# DAC.net
KiCad netlist of a schematic drawn in Altium Designer
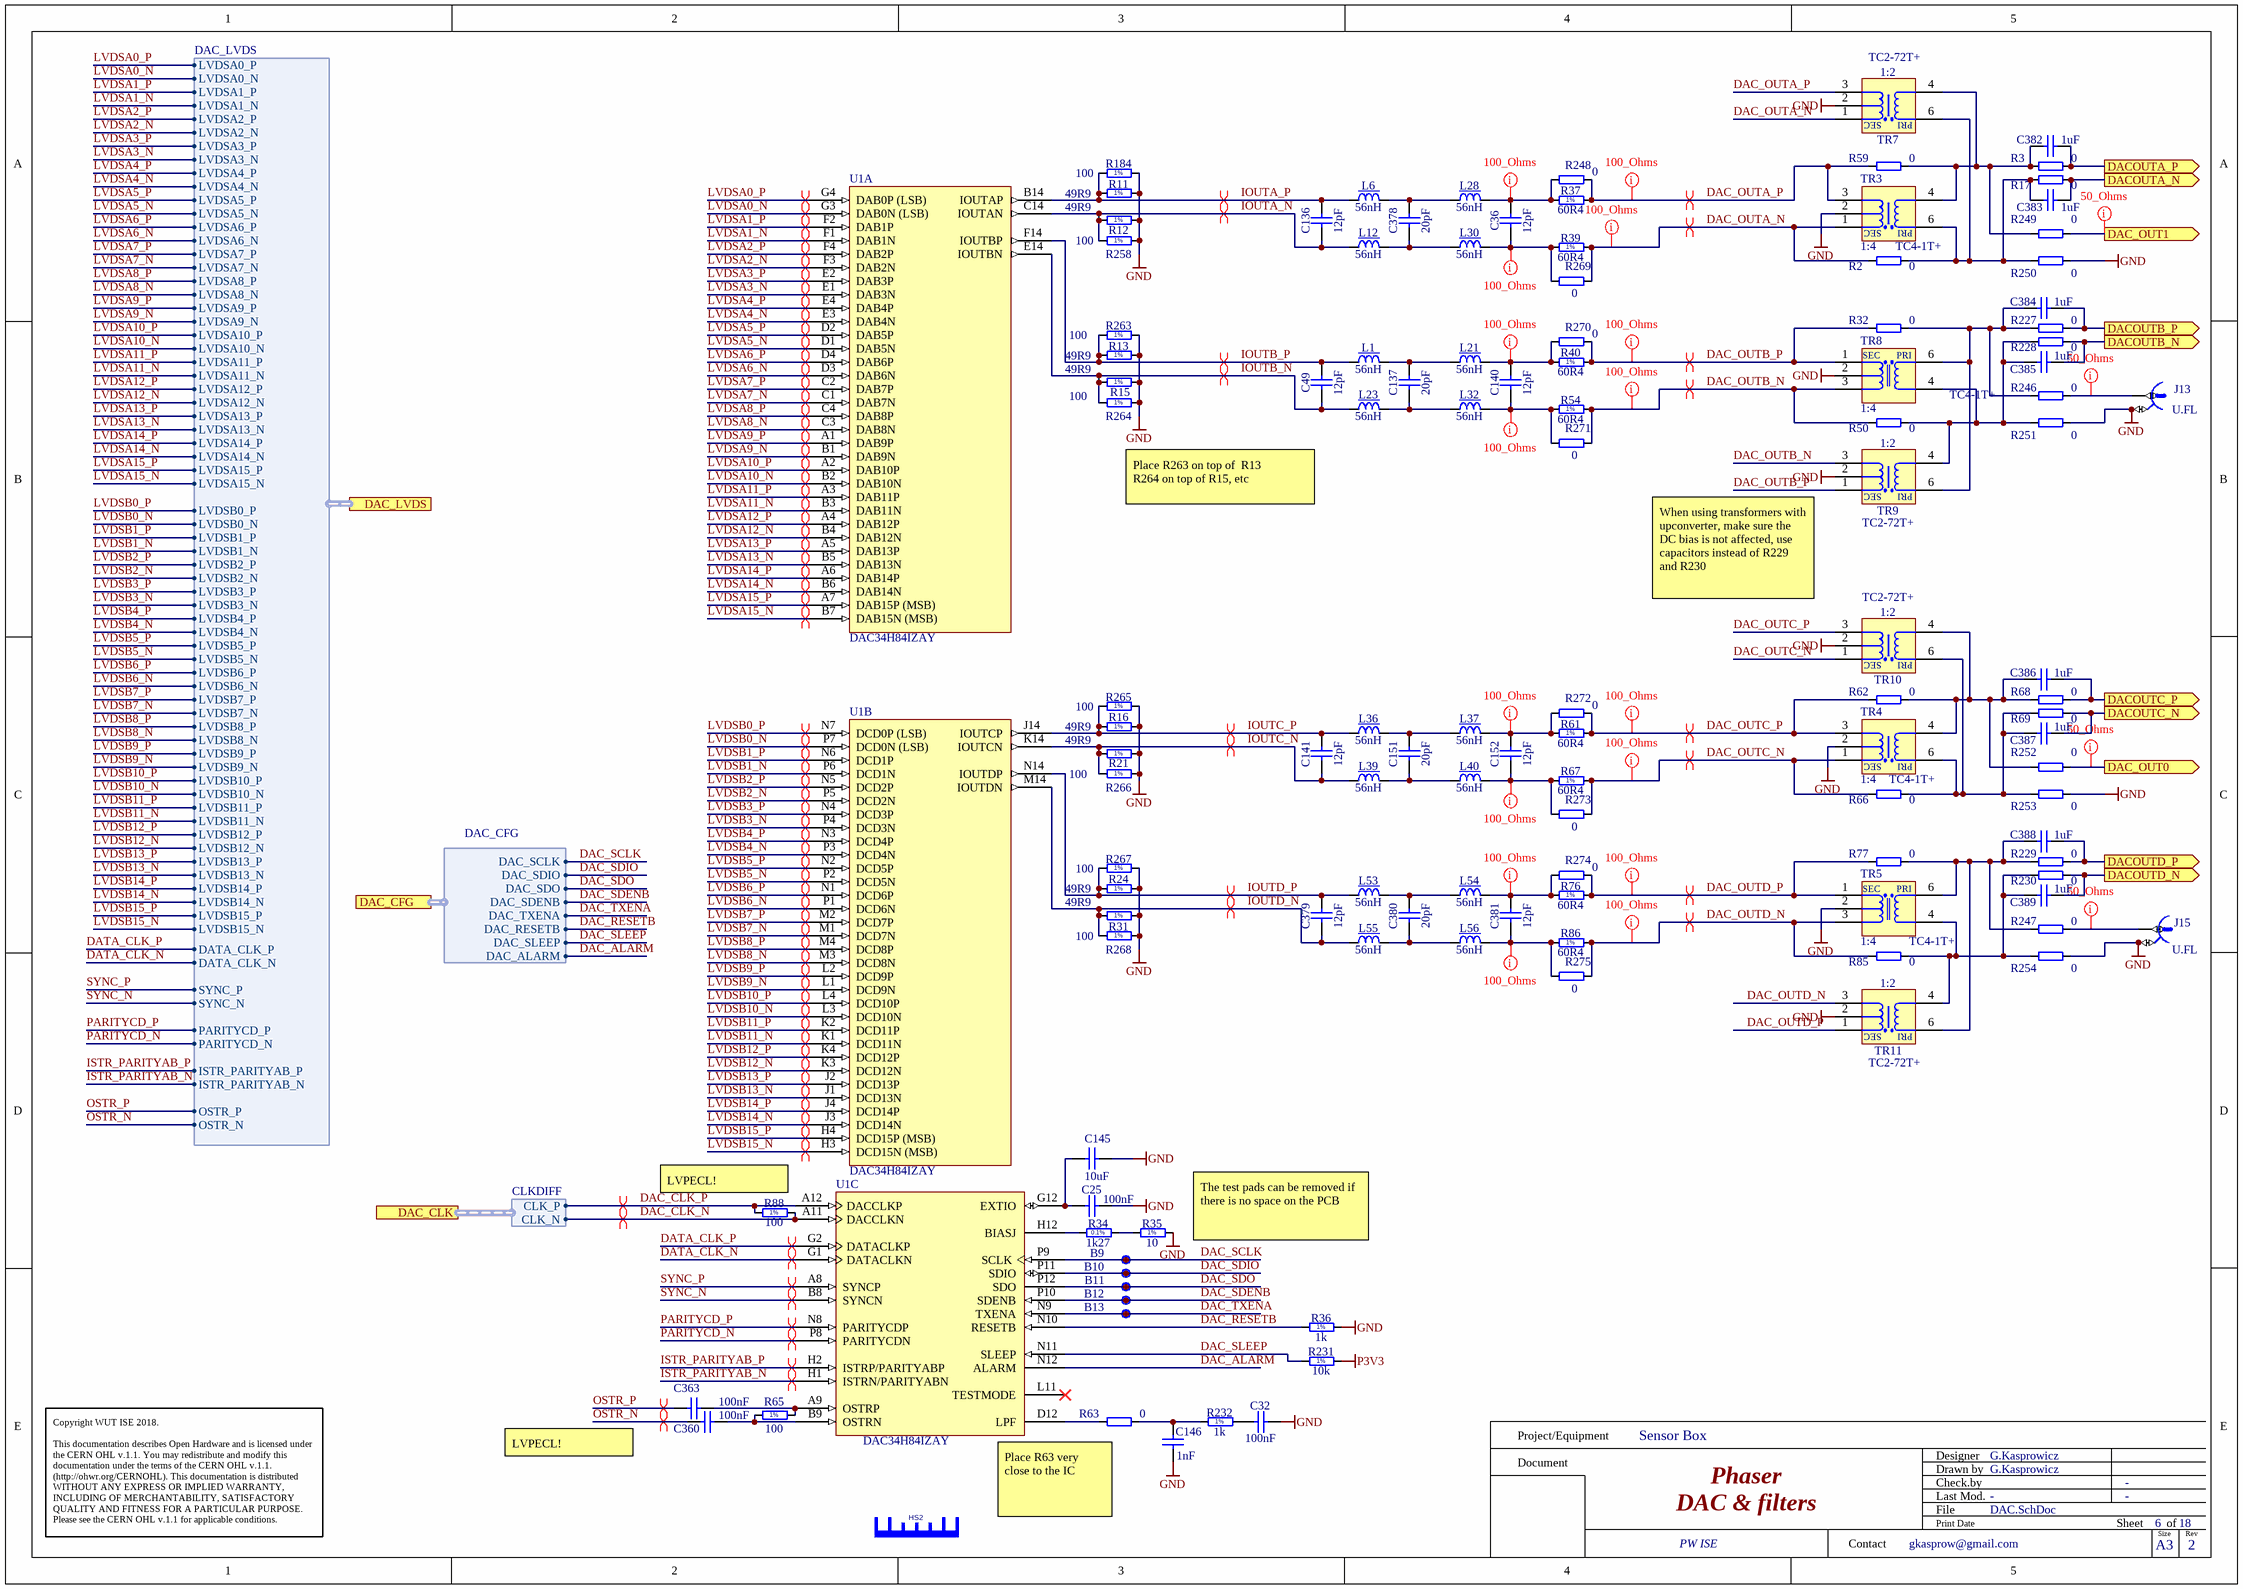
[diagram p0: DAC.SchDoc]

(export (version "E")
  (design (tool "Eeschema 10.0.6"))
  (components
    (comp (ref "B9")
      (value "SMD Pad")
      (footprint "C100")
      (description "Through Hole Pad")
      (fields (field (name "PART NUMBER") "SMD_PAD_D1MM") (field (name "AUTHOR") "CERN DEM JLC"))
      (libsource (lib "Eletro-mechanical") (part "Single SMD Pad (Round)"))
    )
    (comp (ref "B10")
      (value "SMD Pad")
      (footprint "C100")
      (description "Through Hole Pad")
      (fields (field (name "PART NUMBER") "SMD_PAD_D1MM") (field (name "AUTHOR") "CERN DEM JLC"))
      (libsource (lib "Eletro-mechanical") (part "Single SMD Pad (Round)"))
    )
    (comp (ref "B11")
      (value "SMD Pad")
      (footprint "C100")
      (description "Through Hole Pad")
      (fields (field (name "PART NUMBER") "SMD_PAD_D1MM") (field (name "AUTHOR") "CERN DEM JLC"))
      (libsource (lib "Eletro-mechanical") (part "Single SMD Pad (Round)"))
    )
    (comp (ref "B12")
      (value "SMD Pad")
      (footprint "C100")
      (description "Through Hole Pad")
      (fields (field (name "PART NUMBER") "SMD_PAD_D1MM") (field (name "AUTHOR") "CERN DEM JLC"))
      (libsource (lib "Eletro-mechanical") (part "Single SMD Pad (Round)"))
    )
    (comp (ref "B13")
      (value "SMD Pad")
      (footprint "C100")
      (description "Through Hole Pad")
      (fields (field (name "PART NUMBER") "SMD_PAD_D1MM") (field (name "AUTHOR") "CERN DEM JLC"))
      (libsource (lib "Eletro-mechanical") (part "Single SMD Pad (Round)"))
    )
    (comp (ref "C25")
      (value "100nF")
      (footprint "CAPC1005X55N")
      (description "Non-polarised capacitor")
      (fields
        (field (name "PART NUMBER") "CC0402_100NF_16V_10%_X5R")
        (field (name "VOLTAGE") "16V")
        (field (name "AUTHOR") "CERN DEM JLC")
      )
      (libsource (lib "Capacitors") (part "Capacitor - non polarized"))
    )
    (comp (ref "C32")
      (value "100nF")
      (footprint "CAPC1608X90N")
      (description "Non-polarised capacitor")
      (fields
        (field (name "PART NUMBER") "CC0603_100NF_100V_10%_X7R")
        (field (name "VOLTAGE") "100V")
        (field (name "AUTHOR") "CERN DEM JLC")
      )
      (libsource (lib "Capacitors") (part "Capacitor - non polarized"))
    )
    (comp (ref "C36")
      (value "12pF")
      (footprint "CAPC1608X87N")
      (description "Non-polarised capacitor")
      (fields
        (field (name "PART NUMBER") "CC0603_12PF_50V_1%_NP0")
        (field (name "VOLTAGE") "50V")
        (field (name "AUTHOR") "GK")
      )
      (libsource (lib "Passives_RC") (part "CC0603_12PF_50V_1%_NP0"))
    )
    (comp (ref "C49")
      (value "12pF")
      (footprint "CAPC1608X87N")
      (description "Non-polarised capacitor")
      (fields
        (field (name "PART NUMBER") "CC0603_12PF_50V_1%_NP0")
        (field (name "VOLTAGE") "50V")
        (field (name "AUTHOR") "GK")
      )
      (libsource (lib "Passives_RC") (part "CC0603_12PF_50V_1%_NP0"))
    )
    (comp (ref "C136")
      (value "12pF")
      (footprint "CAPC1608X87N")
      (description "Non-polarised capacitor")
      (fields
        (field (name "PART NUMBER") "CC0603_12PF_50V_1%_NP0")
        (field (name "VOLTAGE") "50V")
        (field (name "AUTHOR") "GK")
      )
      (libsource (lib "Passives_RC") (part "CC0603_12PF_50V_1%_NP0"))
    )
    (comp (ref "C137")
      (value "20pF")
      (footprint "CAPC1608X87N")
      (description "Non-polarised capacitor")
      (fields
        (field (name "PART NUMBER") "CC0603_20PF_50V_1%_NP0")
        (field (name "VOLTAGE") "50V")
        (field (name "AUTHOR") "GK")
      )
      (libsource (lib "Passives_RC") (part "CC0603_20PF_50V_1%_NP0"))
    )
    (comp (ref "C140")
      (value "12pF")
      (footprint "CAPC1608X87N")
      (description "Non-polarised capacitor")
      (fields
        (field (name "PART NUMBER") "CC0603_12PF_50V_1%_NP0")
        (field (name "VOLTAGE") "50V")
        (field (name "AUTHOR") "GK")
      )
      (libsource (lib "Passives_RC") (part "CC0603_12PF_50V_1%_NP0"))
    )
    (comp (ref "C141")
      (value "12pF")
      (footprint "CAPC1608X87N")
      (description "Non-polarised capacitor")
      (fields
        (field (name "PART NUMBER") "CC0603_12PF_50V_1%_NP0")
        (field (name "VOLTAGE") "50V")
        (field (name "AUTHOR") "GK")
      )
      (libsource (lib "Passives_RC") (part "CC0603_12PF_50V_1%_NP0"))
    )
    (comp (ref "C145")
      (value "10uF")
      (footprint "CAPC2012X95N")
      (description "Non-polarised capacitor")
      (fields
        (field (name "PART NUMBER") "CC0805_10UF_25V_10%_X5R")
        (field (name "VOLTAGE") "25V")
        (field (name "AUTHOR") "CERN DEM JLC")
      )
      (libsource (lib "Capacitors") (part "Capacitor - non polarized"))
    )
    (comp (ref "C146")
      (value "1nF")
      (footprint "CAPC1608X90N")
      (description "Non-polarised capacitor")
      (fields
        (field (name "PART NUMBER") "CC0603_1NF_50V_1%_NP0")
        (field (name "VOLTAGE") "50V")
        (field (name "AUTHOR") "CERN DEM JLC")
      )
      (libsource (lib "Capacitors") (part "Capacitor - non polarized"))
    )
    (comp (ref "C151")
      (value "20pF")
      (footprint "CAPC1608X87N")
      (description "Non-polarised capacitor")
      (fields
        (field (name "PART NUMBER") "CC0603_20PF_50V_1%_NP0")
        (field (name "VOLTAGE") "50V")
        (field (name "AUTHOR") "GK")
      )
      (libsource (lib "Passives_RC") (part "CC0603_20PF_50V_1%_NP0"))
    )
    (comp (ref "C152")
      (value "12pF")
      (footprint "CAPC1608X87N")
      (description "Non-polarised capacitor")
      (fields
        (field (name "PART NUMBER") "CC0603_12PF_50V_1%_NP0")
        (field (name "VOLTAGE") "50V")
        (field (name "AUTHOR") "GK")
      )
      (libsource (lib "Passives_RC") (part "CC0603_12PF_50V_1%_NP0"))
    )
    (comp (ref "C360")
      (value "100nF")
      (footprint "CAPC1005X55N")
      (description "Non-polarised capacitor")
      (fields
        (field (name "PART NUMBER") "CC0402_100NF_16V_10%_X5R")
        (field (name "VOLTAGE") "16V")
        (field (name "AUTHOR") "CERN DEM JLC")
      )
      (libsource (lib "Capacitors") (part "Capacitor - non polarized"))
    )
    (comp (ref "C363")
      (value "100nF")
      (footprint "CAPC1005X55N")
      (description "Non-polarised capacitor")
      (fields
        (field (name "PART NUMBER") "CC0402_100NF_16V_10%_X5R")
        (field (name "VOLTAGE") "16V")
        (field (name "AUTHOR") "CERN DEM JLC")
      )
      (libsource (lib "Capacitors") (part "Capacitor - non polarized"))
    )
    (comp (ref "C378")
      (value "20pF")
      (footprint "CAPC1608X87N")
      (description "Non-polarised capacitor")
      (fields
        (field (name "PART NUMBER") "CC0603_20PF_50V_1%_NP0")
        (field (name "VOLTAGE") "50V")
        (field (name "AUTHOR") "GK")
      )
      (libsource (lib "Passives_RC") (part "CC0603_20PF_50V_1%_NP0"))
    )
    (comp (ref "C379")
      (value "12pF")
      (footprint "CAPC1608X87N")
      (description "Non-polarised capacitor")
      (fields
        (field (name "PART NUMBER") "CC0603_12PF_50V_1%_NP0")
        (field (name "VOLTAGE") "50V")
        (field (name "AUTHOR") "GK")
      )
      (libsource (lib "Passives_RC") (part "CC0603_12PF_50V_1%_NP0"))
    )
    (comp (ref "C380")
      (value "20pF")
      (footprint "CAPC1608X87N")
      (description "Non-polarised capacitor")
      (fields
        (field (name "PART NUMBER") "CC0603_20PF_50V_1%_NP0")
        (field (name "VOLTAGE") "50V")
        (field (name "AUTHOR") "GK")
      )
      (libsource (lib "Passives_RC") (part "CC0603_20PF_50V_1%_NP0"))
    )
    (comp (ref "C381")
      (value "12pF")
      (footprint "CAPC1608X87N")
      (description "Non-polarised capacitor")
      (fields
        (field (name "PART NUMBER") "CC0603_12PF_50V_1%_NP0")
        (field (name "VOLTAGE") "50V")
        (field (name "AUTHOR") "GK")
      )
      (libsource (lib "Passives_RC") (part "CC0603_12PF_50V_1%_NP0"))
    )
    (comp (ref "C382")
      (value "1uF")
      (footprint "CAPC1005X55N")
      (description "Non-polarised capacitor")
      (fields
        (field (name "PART NUMBER") "CC0402_1UF_16V_10%_X5R")
        (field (name "VOLTAGE") "16V")
        (field (name "AUTHOR") "CERN DEM JLC")
      )
      (libsource (lib "Capacitors") (part "Capacitor - non polarized"))
    )
    (comp (ref "C383")
      (value "1uF")
      (footprint "CAPC1005X55N")
      (description "Non-polarised capacitor")
      (fields
        (field (name "PART NUMBER") "CC0402_1UF_16V_10%_X5R")
        (field (name "VOLTAGE") "16V")
        (field (name "AUTHOR") "CERN DEM JLC")
      )
      (libsource (lib "Capacitors") (part "Capacitor - non polarized"))
    )
    (comp (ref "C384")
      (value "1uF")
      (footprint "CAPC1005X55N")
      (description "Non-polarised capacitor")
      (fields
        (field (name "PART NUMBER") "CC0402_1UF_16V_10%_X5R")
        (field (name "VOLTAGE") "16V")
        (field (name "AUTHOR") "CERN DEM JLC")
      )
      (libsource (lib "Capacitors") (part "Capacitor - non polarized"))
    )
    (comp (ref "C385")
      (value "1uF")
      (footprint "CAPC1005X55N")
      (description "Non-polarised capacitor")
      (fields
        (field (name "PART NUMBER") "CC0402_1UF_16V_10%_X5R")
        (field (name "VOLTAGE") "16V")
        (field (name "AUTHOR") "CERN DEM JLC")
      )
      (libsource (lib "Capacitors") (part "Capacitor - non polarized"))
    )
    (comp (ref "C386")
      (value "1uF")
      (footprint "CAPC1005X55N")
      (description "Non-polarised capacitor")
      (fields
        (field (name "PART NUMBER") "CC0402_1UF_16V_10%_X5R")
        (field (name "VOLTAGE") "16V")
        (field (name "AUTHOR") "CERN DEM JLC")
      )
      (libsource (lib "Capacitors") (part "Capacitor - non polarized"))
    )
    (comp (ref "C387")
      (value "1uF")
      (footprint "CAPC1005X55N")
      (description "Non-polarised capacitor")
      (fields
        (field (name "PART NUMBER") "CC0402_1UF_16V_10%_X5R")
        (field (name "VOLTAGE") "16V")
        (field (name "AUTHOR") "CERN DEM JLC")
      )
      (libsource (lib "Capacitors") (part "Capacitor - non polarized"))
    )
    (comp (ref "C388")
      (value "1uF")
      (footprint "CAPC1005X55N")
      (description "Non-polarised capacitor")
      (fields
        (field (name "PART NUMBER") "CC0402_1UF_16V_10%_X5R")
        (field (name "VOLTAGE") "16V")
        (field (name "AUTHOR") "CERN DEM JLC")
      )
      (libsource (lib "Capacitors") (part "Capacitor - non polarized"))
    )
    (comp (ref "C389")
      (value "1uF")
      (footprint "CAPC1005X55N")
      (description "Non-polarised capacitor")
      (fields
        (field (name "PART NUMBER") "CC0402_1UF_16V_10%_X5R")
        (field (name "VOLTAGE") "16V")
        (field (name "AUTHOR") "CERN DEM JLC")
      )
      (libsource (lib "Capacitors") (part "Capacitor - non polarized"))
    )
    (comp (ref "HS2")
      (value "Heat Sink No Pad")
      (footprint "HSINK_HSB03-121218")
      (description "Rth: 27.5K/W - L 12mm x W 12mm x H 18mm Black Anodized Heatsinks for BGA")
      (fields
        (field (name "PART NUMBER") "HSB03-121218")
        (field (name "MANUFACTURER") "CUI")
        (field (name "AUTHOR") "GK")
      )
      (libsource (lib "Mechanical") (part "HEAT_SINK_BGA_12x12x18"))
    )
    (comp (ref "J13")
      (value "U.FL")
      (footprint "HIROSE_U.FL-R-SMT-1(10)")
      (fields
        (field (name "MANUFACTURER") "HIROSE (HRS)")
        (field (name "MANUFACTURER PART NUMBER") "U.FL-R-SMT-1(10)")
        (field (name "PART NUMBER") "HIROSE_U.FL-R-SMT-1(10)")
        (field (name "AUTHOR") "CERN DEM JLC")
      )
      (libsource (lib "Connectors") (part "Coax_1Male_1Shield"))
    )
    (comp (ref "J15")
      (value "U.FL")
      (footprint "HIROSE_U.FL-R-SMT-1(10)")
      (fields
        (field (name "MANUFACTURER") "HIROSE (HRS)")
        (field (name "MANUFACTURER PART NUMBER") "U.FL-R-SMT-1(10)")
        (field (name "PART NUMBER") "HIROSE_U.FL-R-SMT-1(10)")
        (field (name "AUTHOR") "CERN DEM JLC")
      )
      (libsource (lib "Connectors") (part "Coax_1Male_1Shield"))
    )
    (comp (ref "L1")
      (value "56nH")
      (footprint "IND_MURATA_LQW18AS_0Z")
      (description "Inductor With Core")
      (fields
        (field (name "PART NUMBER") "IND0603_56NH_2%_MURATA_LQW18AS56NG0ZD")
        (field (name "POWER") "600mA")
        (field (name "AUTHOR") "CERN DEM BC")
      )
      (libsource (lib "Inductors & Transformers") (part "Inductor With Magnetic core"))
    )
    (comp (ref "L6")
      (value "56nH")
      (footprint "IND_MURATA_LQW18AS_0Z")
      (description "Inductor With Core")
      (fields
        (field (name "PART NUMBER") "IND0603_56NH_2%_MURATA_LQW18AS56NG0ZD")
        (field (name "POWER") "600mA")
        (field (name "AUTHOR") "CERN DEM BC")
      )
      (libsource (lib "Inductors & Transformers") (part "Inductor With Magnetic core"))
    )
    (comp (ref "L12")
      (value "56nH")
      (footprint "IND_MURATA_LQW18AS_0Z")
      (description "Inductor With Core")
      (fields
        (field (name "PART NUMBER") "IND0603_56NH_2%_MURATA_LQW18AS56NG0ZD")
        (field (name "POWER") "600mA")
        (field (name "AUTHOR") "CERN DEM BC")
      )
      (libsource (lib "Inductors & Transformers") (part "Inductor With Magnetic core"))
    )
    (comp (ref "L21")
      (value "56nH")
      (footprint "IND_MURATA_LQW18AS_0Z")
      (description "Inductor With Core")
      (fields
        (field (name "PART NUMBER") "IND0603_56NH_2%_MURATA_LQW18AS56NG0ZD")
        (field (name "POWER") "600mA")
        (field (name "AUTHOR") "CERN DEM BC")
      )
      (libsource (lib "Inductors & Transformers") (part "Inductor With Magnetic core"))
    )
    (comp (ref "L23")
      (value "56nH")
      (footprint "IND_MURATA_LQW18AS_0Z")
      (description "Inductor With Core")
      (fields
        (field (name "PART NUMBER") "IND0603_56NH_2%_MURATA_LQW18AS56NG0ZD")
        (field (name "POWER") "600mA")
        (field (name "AUTHOR") "CERN DEM BC")
      )
      (libsource (lib "Inductors & Transformers") (part "Inductor With Magnetic core"))
    )
    (comp (ref "L28")
      (value "56nH")
      (footprint "IND_MURATA_LQW18AS_0Z")
      (description "Inductor With Core")
      (fields
        (field (name "PART NUMBER") "IND0603_56NH_2%_MURATA_LQW18AS56NG0ZD")
        (field (name "POWER") "600mA")
        (field (name "AUTHOR") "CERN DEM BC")
      )
      (libsource (lib "Inductors & Transformers") (part "Inductor With Magnetic core"))
    )
    (comp (ref "L30")
      (value "56nH")
      (footprint "IND_MURATA_LQW18AS_0Z")
      (description "Inductor With Core")
      (fields
        (field (name "PART NUMBER") "IND0603_56NH_2%_MURATA_LQW18AS56NG0ZD")
        (field (name "POWER") "600mA")
        (field (name "AUTHOR") "CERN DEM BC")
      )
      (libsource (lib "Inductors & Transformers") (part "Inductor With Magnetic core"))
    )
    (comp (ref "L32")
      (value "56nH")
      (footprint "IND_MURATA_LQW18AS_0Z")
      (description "Inductor With Core")
      (fields
        (field (name "PART NUMBER") "IND0603_56NH_2%_MURATA_LQW18AS56NG0ZD")
        (field (name "POWER") "600mA")
        (field (name "AUTHOR") "CERN DEM BC")
      )
      (libsource (lib "Inductors & Transformers") (part "Inductor With Magnetic core"))
    )
    (comp (ref "L36")
      (value "56nH")
      (footprint "IND_MURATA_LQW18AS_0Z")
      (description "Inductor With Core")
      (fields
        (field (name "PART NUMBER") "IND0603_56NH_2%_MURATA_LQW18AS56NG0ZD")
        (field (name "POWER") "600mA")
        (field (name "AUTHOR") "CERN DEM BC")
      )
      (libsource (lib "Inductors & Transformers") (part "Inductor With Magnetic core"))
    )
    (comp (ref "L37")
      (value "56nH")
      (footprint "IND_MURATA_LQW18AS_0Z")
      (description "Inductor With Core")
      (fields
        (field (name "PART NUMBER") "IND0603_56NH_2%_MURATA_LQW18AS56NG0ZD")
        (field (name "POWER") "600mA")
        (field (name "AUTHOR") "CERN DEM BC")
      )
      (libsource (lib "Inductors & Transformers") (part "Inductor With Magnetic core"))
    )
    (comp (ref "L39")
      (value "56nH")
      (footprint "IND_MURATA_LQW18AS_0Z")
      (description "Inductor With Core")
      (fields
        (field (name "PART NUMBER") "IND0603_56NH_2%_MURATA_LQW18AS56NG0ZD")
        (field (name "POWER") "600mA")
        (field (name "AUTHOR") "CERN DEM BC")
      )
      (libsource (lib "Inductors & Transformers") (part "Inductor With Magnetic core"))
    )
    (comp (ref "L40")
      (value "56nH")
      (footprint "IND_MURATA_LQW18AS_0Z")
      (description "Inductor With Core")
      (fields
        (field (name "PART NUMBER") "IND0603_56NH_2%_MURATA_LQW18AS56NG0ZD")
        (field (name "POWER") "600mA")
        (field (name "AUTHOR") "CERN DEM BC")
      )
      (libsource (lib "Inductors & Transformers") (part "Inductor With Magnetic core"))
    )
    (comp (ref "L53")
      (value "56nH")
      (footprint "IND_MURATA_LQW18AS_0Z")
      (description "Inductor With Core")
      (fields
        (field (name "PART NUMBER") "IND0603_56NH_2%_MURATA_LQW18AS56NG0ZD")
        (field (name "POWER") "600mA")
        (field (name "AUTHOR") "CERN DEM BC")
      )
      (libsource (lib "Inductors & Transformers") (part "Inductor With Magnetic core"))
    )
    (comp (ref "L54")
      (value "56nH")
      (footprint "IND_MURATA_LQW18AS_0Z")
      (description "Inductor With Core")
      (fields
        (field (name "PART NUMBER") "IND0603_56NH_2%_MURATA_LQW18AS56NG0ZD")
        (field (name "POWER") "600mA")
        (field (name "AUTHOR") "CERN DEM BC")
      )
      (libsource (lib "Inductors & Transformers") (part "Inductor With Magnetic core"))
    )
    (comp (ref "L55")
      (value "56nH")
      (footprint "IND_MURATA_LQW18AS_0Z")
      (description "Inductor With Core")
      (fields
        (field (name "PART NUMBER") "IND0603_56NH_2%_MURATA_LQW18AS56NG0ZD")
        (field (name "POWER") "600mA")
        (field (name "AUTHOR") "CERN DEM BC")
      )
      (libsource (lib "Inductors & Transformers") (part "Inductor With Magnetic core"))
    )
    (comp (ref "L56")
      (value "56nH")
      (footprint "IND_MURATA_LQW18AS_0Z")
      (description "Inductor With Core")
      (fields
        (field (name "PART NUMBER") "IND0603_56NH_2%_MURATA_LQW18AS56NG0ZD")
        (field (name "POWER") "600mA")
        (field (name "AUTHOR") "CERN DEM BC")
      )
      (libsource (lib "Inductors & Transformers") (part "Inductor With Magnetic core"))
    )
    (comp (ref "R2")
      (value "0")
      (footprint "RESC1005X40N")
      (description "Resistor")
      (fields
        (field (name "PART NUMBER") "R0402_0R_JUMPER")
        (field (name "MANUFACTURER") "GENERIC")
        (field (name "AUTHOR") "CERN DEM JLC")
      )
      (libsource (lib "Resistors") (part "Resistor"))
    )
    (comp (ref "R3")
      (value "0")
      (footprint "RESC1005X40N")
      (description "Resistor")
      (fields
        (field (name "PART NUMBER") "R0402_0R_JUMPER")
        (field (name "MANUFACTURER") "GENERIC")
        (field (name "AUTHOR") "CERN DEM JLC")
      )
      (libsource (lib "Resistors") (part "Resistor"))
    )
    (comp (ref "R11")
      (value "49R9")
      (footprint "RESC1005X40N")
      (description "Resistor - 1%")
      (fields
        (field (name "PART NUMBER") "R0402_49R9_1%_0.0625W_100PPM")
        (field (name "POWER") "0.0625W")
        (field (name "AUTHOR") "CERN DEM JLC")
      )
      (libsource (lib "Resistors") (part "Resistor - 1%"))
    )
    (comp (ref "R12")
      (value "49R9")
      (footprint "RESC1005X40N")
      (description "Resistor - 1%")
      (fields
        (field (name "PART NUMBER") "R0402_49R9_1%_0.0625W_100PPM")
        (field (name "POWER") "0.0625W")
        (field (name "AUTHOR") "CERN DEM JLC")
      )
      (libsource (lib "Resistors") (part "Resistor - 1%"))
    )
    (comp (ref "R13")
      (value "49R9")
      (footprint "RESC1005X40N")
      (description "Resistor - 1%")
      (fields
        (field (name "PART NUMBER") "R0402_49R9_1%_0.0625W_100PPM")
        (field (name "POWER") "0.0625W")
        (field (name "AUTHOR") "CERN DEM JLC")
      )
      (libsource (lib "Resistors") (part "Resistor - 1%"))
    )
    (comp (ref "R15")
      (value "49R9")
      (footprint "RESC1005X40N")
      (description "Resistor - 1%")
      (fields
        (field (name "PART NUMBER") "R0402_49R9_1%_0.0625W_100PPM")
        (field (name "POWER") "0.0625W")
        (field (name "AUTHOR") "CERN DEM JLC")
      )
      (libsource (lib "Resistors") (part "Resistor - 1%"))
    )
    (comp (ref "R16")
      (value "49R9")
      (footprint "RESC1005X40N")
      (description "Resistor - 1%")
      (fields
        (field (name "PART NUMBER") "R0402_49R9_1%_0.0625W_100PPM")
        (field (name "POWER") "0.0625W")
        (field (name "AUTHOR") "CERN DEM JLC")
      )
      (libsource (lib "Resistors") (part "Resistor - 1%"))
    )
    (comp (ref "R17")
      (value "0")
      (footprint "RESC1005X40N")
      (description "Resistor")
      (fields
        (field (name "PART NUMBER") "R0402_0R_JUMPER")
        (field (name "MANUFACTURER") "GENERIC")
        (field (name "AUTHOR") "CERN DEM JLC")
      )
      (libsource (lib "Resistors") (part "Resistor"))
    )
    (comp (ref "R21")
      (value "49R9")
      (footprint "RESC1005X40N")
      (description "Resistor - 1%")
      (fields
        (field (name "PART NUMBER") "R0402_49R9_1%_0.0625W_100PPM")
        (field (name "POWER") "0.0625W")
        (field (name "AUTHOR") "CERN DEM JLC")
      )
      (libsource (lib "Resistors") (part "Resistor - 1%"))
    )
    (comp (ref "R24")
      (value "49R9")
      (footprint "RESC1005X40N")
      (description "Resistor - 1%")
      (fields
        (field (name "PART NUMBER") "R0402_49R9_1%_0.0625W_100PPM")
        (field (name "POWER") "0.0625W")
        (field (name "AUTHOR") "CERN DEM JLC")
      )
      (libsource (lib "Resistors") (part "Resistor - 1%"))
    )
    (comp (ref "R31")
      (value "49R9")
      (footprint "RESC1005X40N")
      (description "Resistor - 1%")
      (fields
        (field (name "PART NUMBER") "R0402_49R9_1%_0.0625W_100PPM")
        (field (name "POWER") "0.0625W")
        (field (name "AUTHOR") "CERN DEM JLC")
      )
      (libsource (lib "Resistors") (part "Resistor - 1%"))
    )
    (comp (ref "R32")
      (value "0")
      (footprint "RESC1005X40N")
      (description "Resistor")
      (fields
        (field (name "PART NUMBER") "R0402_0R_JUMPER")
        (field (name "MANUFACTURER") "GENERIC")
        (field (name "AUTHOR") "CERN DEM JLC")
      )
      (libsource (lib "Resistors") (part "Resistor"))
    )
    (comp (ref "R34")
      (value "1k27")
      (footprint "RESC1608X55N")
      (description "Resistor - 0.1%")
      (fields
        (field (name "PART NUMBER") "R0603_1K27_0.1%_0.063W_10PPM")
        (field (name "POWER") "0.063W")
        (field (name "AUTHOR") "CERN DEM JLC")
      )
      (libsource (lib "Resistors") (part "Resistor - 0.1%"))
    )
    (comp (ref "R35")
      (value "10")
      (footprint "RESC1005X40N")
      (description "Resistor - 1%")
      (fields
        (field (name "PART NUMBER") "R0402_10R_1%_0.0625W_200PPM")
        (field (name "POWER") "0.0625W")
        (field (name "AUTHOR") "CERN DEM JLC")
      )
      (libsource (lib "Resistors") (part "Resistor - 1%"))
    )
    (comp (ref "R36")
      (value "1k")
      (footprint "RESC1608X55N")
      (description "Resistor - 1%")
      (fields
        (field (name "PART NUMBER") "R0603_1K_1%_0.1W_100PPM")
        (field (name "POWER") "0.1W")
        (field (name "AUTHOR") "CERN DEM JLC")
      )
      (libsource (lib "Resistors") (part "Resistor - 1%"))
    )
    (comp (ref "R37")
      (value "60R4")
      (footprint "RESC1005X40N")
      (description "Resistor - 1%")
      (fields
        (field (name "PART NUMBER") "R0402_60R4_1%_0.0625W_100PPM")
        (field (name "POWER") "0.0625W")
        (field (name "AUTHOR") "GK")
      )
      (libsource (lib "Passives_RC") (part "R0402_60R4_1%_0.0625W_100PPM"))
    )
    (comp (ref "R39")
      (value "60R4")
      (footprint "RESC1005X40N")
      (description "Resistor - 1%")
      (fields
        (field (name "PART NUMBER") "R0402_60R4_1%_0.0625W_100PPM")
        (field (name "POWER") "0.0625W")
        (field (name "AUTHOR") "GK")
      )
      (libsource (lib "Passives_RC") (part "R0402_60R4_1%_0.0625W_100PPM"))
    )
    (comp (ref "R40")
      (value "60R4")
      (footprint "RESC1005X40N")
      (description "Resistor - 1%")
      (fields
        (field (name "PART NUMBER") "R0402_60R4_1%_0.0625W_100PPM")
        (field (name "POWER") "0.0625W")
        (field (name "AUTHOR") "GK")
      )
      (libsource (lib "Passives_RC") (part "R0402_60R4_1%_0.0625W_100PPM"))
    )
    (comp (ref "R50")
      (value "0")
      (footprint "RESC1005X40N")
      (description "Resistor")
      (fields
        (field (name "PART NUMBER") "R0402_0R_JUMPER")
        (field (name "MANUFACTURER") "GENERIC")
        (field (name "AUTHOR") "CERN DEM JLC")
      )
      (libsource (lib "Resistors") (part "Resistor"))
    )
    (comp (ref "R54")
      (value "60R4")
      (footprint "RESC1005X40N")
      (description "Resistor - 1%")
      (fields
        (field (name "PART NUMBER") "R0402_60R4_1%_0.0625W_100PPM")
        (field (name "POWER") "0.0625W")
        (field (name "AUTHOR") "GK")
      )
      (libsource (lib "Passives_RC") (part "R0402_60R4_1%_0.0625W_100PPM"))
    )
    (comp (ref "R59")
      (value "0")
      (footprint "RESC1005X40N")
      (description "Resistor")
      (fields
        (field (name "PART NUMBER") "R0402_0R_JUMPER")
        (field (name "MANUFACTURER") "GENERIC")
        (field (name "AUTHOR") "CERN DEM JLC")
      )
      (libsource (lib "Resistors") (part "Resistor"))
    )
    (comp (ref "R61")
      (value "60R4")
      (footprint "RESC1005X40N")
      (description "Resistor - 1%")
      (fields
        (field (name "PART NUMBER") "R0402_60R4_1%_0.0625W_100PPM")
        (field (name "POWER") "0.0625W")
        (field (name "AUTHOR") "GK")
      )
      (libsource (lib "Passives_RC") (part "R0402_60R4_1%_0.0625W_100PPM"))
    )
    (comp (ref "R62")
      (value "0")
      (footprint "RESC1005X40N")
      (description "Resistor")
      (fields
        (field (name "PART NUMBER") "R0402_0R_JUMPER")
        (field (name "MANUFACTURER") "GENERIC")
        (field (name "AUTHOR") "CERN DEM JLC")
      )
      (libsource (lib "Resistors") (part "Resistor"))
    )
    (comp (ref "R63")
      (value "0")
      (footprint "RESC1005X40N")
      (description "Resistor")
      (fields
        (field (name "PART NUMBER") "R0402_0R_JUMPER")
        (field (name "MANUFACTURER") "GENERIC")
        (field (name "AUTHOR") "CERN DEM JLC")
      )
      (libsource (lib "Resistors") (part "Resistor"))
    )
    (comp (ref "R65")
      (value "100")
      (footprint "RESC0603X28N")
      (description "Resistor - 1%")
      (fields
        (field (name "PART NUMBER") "R0201_100R_1%_0.05W_200PPM")
        (field (name "POWER") "0.05W")
        (field (name "AUTHOR") "CERN DEM JLC")
      )
      (libsource (lib "Resistors") (part "Resistor - 1%"))
    )
    (comp (ref "R66")
      (value "0")
      (footprint "RESC1005X40N")
      (description "Resistor")
      (fields
        (field (name "PART NUMBER") "R0402_0R_JUMPER")
        (field (name "MANUFACTURER") "GENERIC")
        (field (name "AUTHOR") "CERN DEM JLC")
      )
      (libsource (lib "Resistors") (part "Resistor"))
    )
    (comp (ref "R67")
      (value "60R4")
      (footprint "RESC1005X40N")
      (description "Resistor - 1%")
      (fields
        (field (name "PART NUMBER") "R0402_60R4_1%_0.0625W_100PPM")
        (field (name "POWER") "0.0625W")
        (field (name "AUTHOR") "GK")
      )
      (libsource (lib "Passives_RC") (part "R0402_60R4_1%_0.0625W_100PPM"))
    )
    (comp (ref "R68")
      (value "0")
      (footprint "RESC1005X40N")
      (description "Resistor")
      (fields
        (field (name "PART NUMBER") "R0402_0R_JUMPER")
        (field (name "MANUFACTURER") "GENERIC")
        (field (name "AUTHOR") "CERN DEM JLC")
      )
      (libsource (lib "Resistors") (part "Resistor"))
    )
    (comp (ref "R69")
      (value "0")
      (footprint "RESC1005X40N")
      (description "Resistor")
      (fields
        (field (name "PART NUMBER") "R0402_0R_JUMPER")
        (field (name "MANUFACTURER") "GENERIC")
        (field (name "AUTHOR") "CERN DEM JLC")
      )
      (libsource (lib "Resistors") (part "Resistor"))
    )
    (comp (ref "R76")
      (value "60R4")
      (footprint "RESC1005X40N")
      (description "Resistor - 1%")
      (fields
        (field (name "PART NUMBER") "R0402_60R4_1%_0.0625W_100PPM")
        (field (name "POWER") "0.0625W")
        (field (name "AUTHOR") "GK")
      )
      (libsource (lib "Passives_RC") (part "R0402_60R4_1%_0.0625W_100PPM"))
    )
    (comp (ref "R77")
      (value "0")
      (footprint "RESC1005X40N")
      (description "Resistor")
      (fields
        (field (name "PART NUMBER") "R0402_0R_JUMPER")
        (field (name "MANUFACTURER") "GENERIC")
        (field (name "AUTHOR") "CERN DEM JLC")
      )
      (libsource (lib "Resistors") (part "Resistor"))
    )
    (comp (ref "R85")
      (value "0")
      (footprint "RESC1005X40N")
      (description "Resistor")
      (fields
        (field (name "PART NUMBER") "R0402_0R_JUMPER")
        (field (name "MANUFACTURER") "GENERIC")
        (field (name "AUTHOR") "CERN DEM JLC")
      )
      (libsource (lib "Resistors") (part "Resistor"))
    )
    (comp (ref "R86")
      (value "60R4")
      (footprint "RESC1005X40N")
      (description "Resistor - 1%")
      (fields
        (field (name "PART NUMBER") "R0402_60R4_1%_0.0625W_100PPM")
        (field (name "POWER") "0.0625W")
        (field (name "AUTHOR") "GK")
      )
      (libsource (lib "Passives_RC") (part "R0402_60R4_1%_0.0625W_100PPM"))
    )
    (comp (ref "R88")
      (value "100")
      (footprint "RESC0603X28N")
      (description "Resistor - 1%")
      (fields
        (field (name "PART NUMBER") "R0201_100R_1%_0.05W_200PPM")
        (field (name "POWER") "0.05W")
        (field (name "AUTHOR") "CERN DEM JLC")
      )
      (libsource (lib "Resistors") (part "Resistor - 1%"))
    )
    (comp (ref "R184")
      (value "100")
      (footprint "RESC1005X40N")
      (description "Resistor - 1%")
      (fields
        (field (name "PART NUMBER") "R0402_100R_1%_0.1W_100PPM")
        (field (name "POWER") "0.1W")
        (field (name "AUTHOR") "CERN DEM JLC")
      )
      (libsource (lib "Resistors") (part "Resistor - 1%"))
    )
    (comp (ref "R227")
      (value "0")
      (footprint "RESC1005X40N")
      (description "Resistor")
      (fields
        (field (name "PART NUMBER") "R0402_0R_JUMPER")
        (field (name "MANUFACTURER") "GENERIC")
        (field (name "AUTHOR") "CERN DEM JLC")
      )
      (libsource (lib "Resistors") (part "Resistor"))
    )
    (comp (ref "R228")
      (value "0")
      (footprint "RESC1005X40N")
      (description "Resistor")
      (fields
        (field (name "PART NUMBER") "R0402_0R_JUMPER")
        (field (name "MANUFACTURER") "GENERIC")
        (field (name "AUTHOR") "CERN DEM JLC")
      )
      (libsource (lib "Resistors") (part "Resistor"))
    )
    (comp (ref "R229")
      (value "0")
      (footprint "RESC1005X40N")
      (description "Resistor")
      (fields
        (field (name "PART NUMBER") "R0402_0R_JUMPER")
        (field (name "MANUFACTURER") "GENERIC")
        (field (name "AUTHOR") "CERN DEM JLC")
      )
      (libsource (lib "Resistors") (part "Resistor"))
    )
    (comp (ref "R230")
      (value "0")
      (footprint "RESC1005X40N")
      (description "Resistor")
      (fields
        (field (name "PART NUMBER") "R0402_0R_JUMPER")
        (field (name "MANUFACTURER") "GENERIC")
        (field (name "AUTHOR") "CERN DEM JLC")
      )
      (libsource (lib "Resistors") (part "Resistor"))
    )
    (comp (ref "R231")
      (value "10k")
      (footprint "RESC1608X55N")
      (description "Resistor - 1%")
      (fields
        (field (name "PART NUMBER") "R0603_10K_1%_0.1W_100PPM")
        (field (name "POWER") "0.1W")
        (field (name "AUTHOR") "CERN DEM JLC")
      )
      (libsource (lib "Resistors") (part "Resistor - 1%"))
    )
    (comp (ref "R232")
      (value "1k")
      (footprint "RESC1608X55N")
      (description "Resistor - 1%")
      (fields
        (field (name "PART NUMBER") "R0603_1K_1%_0.1W_100PPM")
        (field (name "POWER") "0.1W")
        (field (name "AUTHOR") "CERN DEM JLC")
      )
      (libsource (lib "Resistors") (part "Resistor - 1%"))
    )
    (comp (ref "R246")
      (value "0")
      (footprint "RESC1005X40N")
      (description "Resistor")
      (fields
        (field (name "PART NUMBER") "R0402_0R_JUMPER")
        (field (name "MANUFACTURER") "GENERIC")
        (field (name "AUTHOR") "CERN DEM JLC")
      )
      (libsource (lib "Resistors") (part "Resistor"))
    )
    (comp (ref "R247")
      (value "0")
      (footprint "RESC1005X40N")
      (description "Resistor")
      (fields
        (field (name "PART NUMBER") "R0402_0R_JUMPER")
        (field (name "MANUFACTURER") "GENERIC")
        (field (name "AUTHOR") "CERN DEM JLC")
      )
      (libsource (lib "Resistors") (part "Resistor"))
    )
    (comp (ref "R248")
      (value "0")
      (footprint "RESC1005X40N")
      (description "Resistor")
      (fields
        (field (name "PART NUMBER") "R0402_0R_JUMPER")
        (field (name "MANUFACTURER") "GENERIC")
        (field (name "AUTHOR") "CERN DEM JLC")
      )
      (libsource (lib "Resistors") (part "Resistor"))
    )
    (comp (ref "R249")
      (value "0")
      (footprint "RESC1005X40N")
      (description "Resistor")
      (fields
        (field (name "PART NUMBER") "R0402_0R_JUMPER")
        (field (name "MANUFACTURER") "GENERIC")
        (field (name "AUTHOR") "CERN DEM JLC")
      )
      (libsource (lib "Resistors") (part "Resistor"))
    )
    (comp (ref "R250")
      (value "0")
      (footprint "RESC1005X40N")
      (description "Resistor")
      (fields
        (field (name "PART NUMBER") "R0402_0R_JUMPER")
        (field (name "MANUFACTURER") "GENERIC")
        (field (name "AUTHOR") "CERN DEM JLC")
      )
      (libsource (lib "Resistors") (part "Resistor"))
    )
    (comp (ref "R251")
      (value "0")
      (footprint "RESC1005X40N")
      (description "Resistor")
      (fields
        (field (name "PART NUMBER") "R0402_0R_JUMPER")
        (field (name "MANUFACTURER") "GENERIC")
        (field (name "AUTHOR") "CERN DEM JLC")
      )
      (libsource (lib "Resistors") (part "Resistor"))
    )
    (comp (ref "R252")
      (value "0")
      (footprint "RESC1005X40N")
      (description "Resistor")
      (fields
        (field (name "PART NUMBER") "R0402_0R_JUMPER")
        (field (name "MANUFACTURER") "GENERIC")
        (field (name "AUTHOR") "CERN DEM JLC")
      )
      (libsource (lib "Resistors") (part "Resistor"))
    )
    (comp (ref "R253")
      (value "0")
      (footprint "RESC1005X40N")
      (description "Resistor")
      (fields
        (field (name "PART NUMBER") "R0402_0R_JUMPER")
        (field (name "MANUFACTURER") "GENERIC")
        (field (name "AUTHOR") "CERN DEM JLC")
      )
      (libsource (lib "Resistors") (part "Resistor"))
    )
    (comp (ref "R254")
      (value "0")
      (footprint "RESC1005X40N")
      (description "Resistor")
      (fields
        (field (name "PART NUMBER") "R0402_0R_JUMPER")
        (field (name "MANUFACTURER") "GENERIC")
        (field (name "AUTHOR") "CERN DEM JLC")
      )
      (libsource (lib "Resistors") (part "Resistor"))
    )
    (comp (ref "R258")
      (value "100")
      (footprint "RESC1005X40N")
      (description "Resistor - 1%")
      (fields
        (field (name "PART NUMBER") "R0402_100R_1%_0.1W_100PPM")
        (field (name "POWER") "0.1W")
        (field (name "AUTHOR") "CERN DEM JLC")
      )
      (libsource (lib "Resistors") (part "Resistor - 1%"))
    )
    (comp (ref "R263")
      (value "100")
      (footprint "RESC1005X40N")
      (description "Resistor - 1%")
      (fields
        (field (name "PART NUMBER") "R0402_100R_1%_0.1W_100PPM")
        (field (name "POWER") "0.1W")
        (field (name "AUTHOR") "CERN DEM JLC")
      )
      (libsource (lib "Resistors") (part "Resistor - 1%"))
    )
    (comp (ref "R264")
      (value "100")
      (footprint "RESC1005X40N")
      (description "Resistor - 1%")
      (fields
        (field (name "PART NUMBER") "R0402_100R_1%_0.1W_100PPM")
        (field (name "POWER") "0.1W")
        (field (name "AUTHOR") "CERN DEM JLC")
      )
      (libsource (lib "Resistors") (part "Resistor - 1%"))
    )
    (comp (ref "R265")
      (value "100")
      (footprint "RESC1005X40N")
      (description "Resistor - 1%")
      (fields
        (field (name "PART NUMBER") "R0402_100R_1%_0.1W_100PPM")
        (field (name "POWER") "0.1W")
        (field (name "AUTHOR") "CERN DEM JLC")
      )
      (libsource (lib "Resistors") (part "Resistor - 1%"))
    )
    (comp (ref "R266")
      (value "100")
      (footprint "RESC1005X40N")
      (description "Resistor - 1%")
      (fields
        (field (name "PART NUMBER") "R0402_100R_1%_0.1W_100PPM")
        (field (name "POWER") "0.1W")
        (field (name "AUTHOR") "CERN DEM JLC")
      )
      (libsource (lib "Resistors") (part "Resistor - 1%"))
    )
    (comp (ref "R267")
      (value "100")
      (footprint "RESC1005X40N")
      (description "Resistor - 1%")
      (fields
        (field (name "PART NUMBER") "R0402_100R_1%_0.1W_100PPM")
        (field (name "POWER") "0.1W")
        (field (name "AUTHOR") "CERN DEM JLC")
      )
      (libsource (lib "Resistors") (part "Resistor - 1%"))
    )
    (comp (ref "R268")
      (value "100")
      (footprint "RESC1005X40N")
      (description "Resistor - 1%")
      (fields
        (field (name "PART NUMBER") "R0402_100R_1%_0.1W_100PPM")
        (field (name "POWER") "0.1W")
        (field (name "AUTHOR") "CERN DEM JLC")
      )
      (libsource (lib "Resistors") (part "Resistor - 1%"))
    )
    (comp (ref "R269")
      (value "0")
      (footprint "RESC1005X40N")
      (description "Resistor")
      (fields
        (field (name "PART NUMBER") "R0402_0R_JUMPER")
        (field (name "MANUFACTURER") "GENERIC")
        (field (name "AUTHOR") "CERN DEM JLC")
      )
      (libsource (lib "Resistors") (part "Resistor"))
    )
    (comp (ref "R270")
      (value "0")
      (footprint "RESC1005X40N")
      (description "Resistor")
      (fields
        (field (name "PART NUMBER") "R0402_0R_JUMPER")
        (field (name "MANUFACTURER") "GENERIC")
        (field (name "AUTHOR") "CERN DEM JLC")
      )
      (libsource (lib "Resistors") (part "Resistor"))
    )
    (comp (ref "R271")
      (value "0")
      (footprint "RESC1005X40N")
      (description "Resistor")
      (fields
        (field (name "PART NUMBER") "R0402_0R_JUMPER")
        (field (name "MANUFACTURER") "GENERIC")
        (field (name "AUTHOR") "CERN DEM JLC")
      )
      (libsource (lib "Resistors") (part "Resistor"))
    )
    (comp (ref "R272")
      (value "0")
      (footprint "RESC1005X40N")
      (description "Resistor")
      (fields
        (field (name "PART NUMBER") "R0402_0R_JUMPER")
        (field (name "MANUFACTURER") "GENERIC")
        (field (name "AUTHOR") "CERN DEM JLC")
      )
      (libsource (lib "Resistors") (part "Resistor"))
    )
    (comp (ref "R273")
      (value "0")
      (footprint "RESC1005X40N")
      (description "Resistor")
      (fields
        (field (name "PART NUMBER") "R0402_0R_JUMPER")
        (field (name "MANUFACTURER") "GENERIC")
        (field (name "AUTHOR") "CERN DEM JLC")
      )
      (libsource (lib "Resistors") (part "Resistor"))
    )
    (comp (ref "R274")
      (value "0")
      (footprint "RESC1005X40N")
      (description "Resistor")
      (fields
        (field (name "PART NUMBER") "R0402_0R_JUMPER")
        (field (name "MANUFACTURER") "GENERIC")
        (field (name "AUTHOR") "CERN DEM JLC")
      )
      (libsource (lib "Resistors") (part "Resistor"))
    )
    (comp (ref "R275")
      (value "0")
      (footprint "RESC1005X40N")
      (description "Resistor")
      (fields
        (field (name "PART NUMBER") "R0402_0R_JUMPER")
        (field (name "MANUFACTURER") "GENERIC")
        (field (name "AUTHOR") "CERN DEM JLC")
      )
      (libsource (lib "Resistors") (part "Resistor"))
    )
    (comp (ref "TR3")
      (value "1:4")
      (footprint "XFMR_MINI-CIRCUITS_AT224")
      (description "50 Ohms 0.5 to 300 MHz RF Transformer")
      (fields
        (field (name "PART NUMBER") "XFMR_MINI-CIRCUITS_TC4-1T+")
        (field (name "MANUFACTURER") "MINI-CIRCUITS")
        (field (name "MANUFACTURER PART NUMBER") "TC4-1T+")
        (field (name "AUTHOR") "GK")
      )
      (libsource (lib "") (part "XFMR_MINI-CIRCUITS_TC4-1T+_1"))
    )
    (comp (ref "TR4")
      (value "1:4")
      (footprint "XFMR_MINI-CIRCUITS_AT224")
      (description "50 Ohms 0.5 to 300 MHz RF Transformer")
      (fields
        (field (name "PART NUMBER") "XFMR_MINI-CIRCUITS_TC4-1T+")
        (field (name "MANUFACTURER") "MINI-CIRCUITS")
        (field (name "MANUFACTURER PART NUMBER") "TC4-1T+")
        (field (name "AUTHOR") "GK")
      )
      (libsource (lib "") (part "XFMR_MINI-CIRCUITS_TC4-1T+_1"))
    )
    (comp (ref "TR5")
      (value "1:4")
      (footprint "XFMR_MINI-CIRCUITS_AT224")
      (description "50 Ohms 0.5 to 300 MHz RF Transformer")
      (fields
        (field (name "PART NUMBER") "XFMR_MINI-CIRCUITS_TC4-1T+")
        (field (name "MANUFACTURER") "MINI-CIRCUITS")
        (field (name "MANUFACTURER PART NUMBER") "TC4-1T+")
        (field (name "AUTHOR") "GK")
      )
      (libsource (lib "Inductors_Transformers") (part "XFMR_MINI-CIRCUITS_TC4-1T+"))
    )
    (comp (ref "TR7")
      (value "1:2")
      (footprint "XFMR_MINI-CIRCUITS_AT1521")
      (description "50 Ohms 10 to 700MHz RF Transformer")
      (fields
        (field (name "PART NUMBER") "XFMR_MINI-CIRCUITS_TC2-72T+")
        (field (name "MANUFACTURER") "MINI-CIRCUITS")
        (field (name "MANUFACTURER PART NUMBER") "TC2-72T+")
        (field (name "AUTHOR") "CERN DEM BC")
      )
      (libsource (lib "Inductors & Transformers") (part "XFMR_MINI-CIRCUITS_TC2-72T+"))
    )
    (comp (ref "TR8")
      (value "1:4")
      (footprint "XFMR_MINI-CIRCUITS_AT224")
      (description "50 Ohms 0.5 to 300 MHz RF Transformer")
      (fields
        (field (name "PART NUMBER") "XFMR_MINI-CIRCUITS_TC4-1T+")
        (field (name "MANUFACTURER") "MINI-CIRCUITS")
        (field (name "MANUFACTURER PART NUMBER") "TC4-1T+")
        (field (name "AUTHOR") "GK")
      )
      (libsource (lib "Inductors_Transformers") (part "XFMR_MINI-CIRCUITS_TC4-1T+"))
    )
    (comp (ref "TR9")
      (value "1:2")
      (footprint "XFMR_MINI-CIRCUITS_AT1521")
      (description "50 Ohms 10 to 700MHz RF Transformer")
      (fields
        (field (name "PART NUMBER") "XFMR_MINI-CIRCUITS_TC2-72T+")
        (field (name "MANUFACTURER") "MINI-CIRCUITS")
        (field (name "MANUFACTURER PART NUMBER") "TC2-72T+")
        (field (name "AUTHOR") "CERN DEM BC")
      )
      (libsource (lib "Inductors & Transformers") (part "XFMR_MINI-CIRCUITS_TC2-72T+"))
    )
    (comp (ref "TR10")
      (value "1:2")
      (footprint "XFMR_MINI-CIRCUITS_AT1521")
      (description "50 Ohms 10 to 700MHz RF Transformer")
      (fields
        (field (name "PART NUMBER") "XFMR_MINI-CIRCUITS_TC2-72T+")
        (field (name "MANUFACTURER") "MINI-CIRCUITS")
        (field (name "MANUFACTURER PART NUMBER") "TC2-72T+")
        (field (name "AUTHOR") "CERN DEM BC")
      )
      (libsource (lib "Inductors & Transformers") (part "XFMR_MINI-CIRCUITS_TC2-72T+"))
    )
    (comp (ref "TR11")
      (value "1:2")
      (footprint "XFMR_MINI-CIRCUITS_AT1521")
      (description "50 Ohms 10 to 700MHz RF Transformer")
      (fields
        (field (name "PART NUMBER") "XFMR_MINI-CIRCUITS_TC2-72T+")
        (field (name "MANUFACTURER") "MINI-CIRCUITS")
        (field (name "MANUFACTURER PART NUMBER") "TC2-72T+")
        (field (name "AUTHOR") "CERN DEM BC")
      )
      (libsource (lib "Inductors & Transformers") (part "XFMR_MINI-CIRCUITS_TC2-72T+"))
    )
    (comp (ref "U1")
      (value "DAC34H84IZAY")
      (footprint "TI-ZAY196")
      (description "Quad-Channel, 16-Bit, 1.5 GSPS DAC, -40 to 85 degC, 196-pin BGA (ZAY196), Green (RoHS & no Sb/Br)")
      (fields (field (name "MANUFACTURER") "Texas Instruments"))
      (libsource (lib "Altium Content Vault") (part "TI-DAC34H_SH84-ZAY196"))
    )
  )
  (nets
    (net (code "4") (name "/DACOUTA_N") (class "Default")
      (node (ref "C383") (pin "2") (pinfunction "2_2") (pintype "passive"))
      (node (ref "R17") (pin "1") (pinfunction "1_1") (pintype "passive"))
    )
    (net (code "5") (name "/DACOUTA_P") (class "Default")
      (node (ref "C382") (pin "2") (pinfunction "2_2") (pintype "passive"))
      (node (ref "R3") (pin "1") (pinfunction "1_1") (pintype "passive"))
    )
    (net (code "6") (name "/DACOUTB_N") (class "Default")
      (node (ref "C385") (pin "2") (pinfunction "2_2") (pintype "passive"))
      (node (ref "R228") (pin "1") (pinfunction "1_1") (pintype "passive"))
    )
    (net (code "7") (name "/DACOUTB_P") (class "Default")
      (node (ref "C384") (pin "2") (pinfunction "2_2") (pintype "passive"))
      (node (ref "R227") (pin "1") (pinfunction "1_1") (pintype "passive"))
    )
    (net (code "8") (name "/DACOUTC_N") (class "Default")
      (node (ref "C387") (pin "2") (pinfunction "2_2") (pintype "passive"))
      (node (ref "R69") (pin "1") (pinfunction "1_1") (pintype "passive"))
    )
    (net (code "9") (name "/DACOUTC_P") (class "Default")
      (node (ref "C386") (pin "2") (pinfunction "2_2") (pintype "passive"))
      (node (ref "R68") (pin "1") (pinfunction "1_1") (pintype "passive"))
    )
    (net (code "10") (name "/DACOUTD_N") (class "Default")
      (node (ref "C389") (pin "2") (pinfunction "2_2") (pintype "passive"))
      (node (ref "R230") (pin "1") (pinfunction "1_1") (pintype "passive"))
    )
    (net (code "11") (name "/DACOUTD_P") (class "Default")
      (node (ref "C388") (pin "2") (pinfunction "2_2") (pintype "passive"))
      (node (ref "R229") (pin "1") (pinfunction "1_1") (pintype "passive"))
    )
    (net (code "12") (name "/DAC_ALARM") (class "Default")
      (node (ref "U1") (pin "N12") (pinfunction "ALARM_N12") (pintype "tri_state"))
    )
    (net (code "13") (name "/DAC_CLK_N") (class "Default")
      (node (ref "R88") (pin "2") (pinfunction "2_2") (pintype "passive"))
      (node (ref "U1") (pin "A11") (pinfunction "DACCLKN_A11") (pintype "input"))
    )
    (net (code "14") (name "/DAC_CLK_P") (class "Default")
      (node (ref "R88") (pin "1") (pinfunction "1_1") (pintype "passive"))
      (node (ref "U1") (pin "A12") (pinfunction "DACCLKP_A12") (pintype "input"))
    )
    (net (code "15") (name "/DAC_OUT0") (class "Default")
      (node (ref "R252") (pin "1") (pinfunction "1_1") (pintype "passive"))
    )
    (net (code "16") (name "/DAC_OUT1") (class "Default")
      (node (ref "R249") (pin "1") (pinfunction "1_1") (pintype "passive"))
    )
    (net (code "17") (name "/DAC_OUTA_N") (class "Default")
      (node (ref "R2") (pin "2") (pinfunction "2_2") (pintype "passive"))
      (node (ref "R269") (pin "1") (pinfunction "1_1") (pintype "passive"))
      (node (ref "R39") (pin "2") (pinfunction "2_2") (pintype "passive"))
      (node (ref "TR3") (pin "1") (pinfunction "SDOT_1") (pintype "passive"))
      (node (ref "TR7") (pin "1") (pinfunction "SDOT_1") (pintype "passive"))
    )
    (net (code "18") (name "/DAC_OUTA_P") (class "Default")
      (node (ref "R248") (pin "1") (pinfunction "1_1") (pintype "passive"))
      (node (ref "R37") (pin "2") (pinfunction "2_2") (pintype "passive"))
      (node (ref "R59") (pin "2") (pinfunction "2_2") (pintype "passive"))
      (node (ref "TR3") (pin "3") (pinfunction "S_3") (pintype "passive"))
      (node (ref "TR7") (pin "3") (pinfunction "S_3") (pintype "passive"))
    )
    (net (code "19") (name "/DAC_OUTB_N") (class "Default")
      (node (ref "R271") (pin "1") (pinfunction "1_1") (pintype "passive"))
      (node (ref "R50") (pin "2") (pinfunction "2_2") (pintype "passive"))
      (node (ref "R54") (pin "2") (pinfunction "2_2") (pintype "passive"))
      (node (ref "TR8") (pin "3") (pinfunction "S_3") (pintype "passive"))
      (node (ref "TR9") (pin "3") (pinfunction "S_3") (pintype "passive"))
    )
    (net (code "20") (name "/DAC_OUTB_P") (class "Default")
      (node (ref "R270") (pin "1") (pinfunction "1_1") (pintype "passive"))
      (node (ref "R32") (pin "2") (pinfunction "2_2") (pintype "passive"))
      (node (ref "R40") (pin "2") (pinfunction "2_2") (pintype "passive"))
      (node (ref "TR8") (pin "1") (pinfunction "SDOT_1") (pintype "passive"))
      (node (ref "TR9") (pin "1") (pinfunction "SDOT_1") (pintype "passive"))
    )
    (net (code "21") (name "/DAC_OUTC_N") (class "Default")
      (node (ref "R273") (pin "1") (pinfunction "1_1") (pintype "passive"))
      (node (ref "R66") (pin "2") (pinfunction "2_2") (pintype "passive"))
      (node (ref "R67") (pin "2") (pinfunction "2_2") (pintype "passive"))
      (node (ref "TR10") (pin "1") (pinfunction "SDOT_1") (pintype "passive"))
      (node (ref "TR4") (pin "1") (pinfunction "SDOT_1") (pintype "passive"))
    )
    (net (code "22") (name "/DAC_OUTC_P") (class "Default")
      (node (ref "R272") (pin "1") (pinfunction "1_1") (pintype "passive"))
      (node (ref "R61") (pin "2") (pinfunction "2_2") (pintype "passive"))
      (node (ref "R62") (pin "2") (pinfunction "2_2") (pintype "passive"))
      (node (ref "TR10") (pin "3") (pinfunction "S_3") (pintype "passive"))
      (node (ref "TR4") (pin "3") (pinfunction "S_3") (pintype "passive"))
    )
    (net (code "23") (name "/DAC_OUTD_N") (class "Default")
      (node (ref "R275") (pin "1") (pinfunction "1_1") (pintype "passive"))
      (node (ref "R85") (pin "2") (pinfunction "2_2") (pintype "passive"))
      (node (ref "R86") (pin "2") (pinfunction "2_2") (pintype "passive"))
      (node (ref "TR11") (pin "3") (pinfunction "S_3") (pintype "passive"))
      (node (ref "TR5") (pin "3") (pinfunction "S_3") (pintype "passive"))
    )
    (net (code "24") (name "/DAC_OUTD_P") (class "Default")
      (node (ref "R274") (pin "1") (pinfunction "1_1") (pintype "passive"))
      (node (ref "R76") (pin "2") (pinfunction "2_2") (pintype "passive"))
      (node (ref "R77") (pin "2") (pinfunction "2_2") (pintype "passive"))
      (node (ref "TR11") (pin "1") (pinfunction "SDOT_1") (pintype "passive"))
      (node (ref "TR5") (pin "1") (pinfunction "SDOT_1") (pintype "passive"))
    )
    (net (code "25") (name "/DAC_RESETB") (class "Default")
      (node (ref "R36") (pin "1") (pinfunction "1_1") (pintype "passive"))
      (node (ref "U1") (pin "N10") (pinfunction "RESETB_N10") (pintype "input"))
    )
    (net (code "26") (name "/DAC_SCLK") (class "Default")
      (node (ref "B9") (pin "1") (pinfunction "1_1") (pintype "bidirectional"))
      (node (ref "U1") (pin "P9") (pinfunction "SCLK_P9") (pintype "input"))
    )
    (net (code "27") (name "/DAC_SDENB") (class "Default")
      (node (ref "B12") (pin "1") (pinfunction "1_1") (pintype "bidirectional"))
      (node (ref "U1") (pin "P10") (pinfunction "SDENB_P10") (pintype "input"))
    )
    (net (code "28") (name "/DAC_SDIO") (class "Default")
      (node (ref "B10") (pin "1") (pinfunction "1_1") (pintype "bidirectional"))
      (node (ref "U1") (pin "P11") (pinfunction "SDIO_P11") (pintype "bidirectional"))
    )
    (net (code "29") (name "/DAC_SDO") (class "Default")
      (node (ref "B11") (pin "1") (pinfunction "1_1") (pintype "bidirectional"))
      (node (ref "U1") (pin "P12") (pinfunction "SDO_P12") (pintype "tri_state"))
    )
    (net (code "30") (name "/DAC_SLEEP") (class "Default")
      (node (ref "R231") (pin "1") (pinfunction "1_1") (pintype "passive"))
      (node (ref "U1") (pin "N11") (pinfunction "SLEEP_N11") (pintype "input"))
    )
    (net (code "31") (name "/DAC_TXENA") (class "Default")
      (node (ref "B13") (pin "1") (pinfunction "1_1") (pintype "bidirectional"))
      (node (ref "U1") (pin "N9") (pinfunction "TXENA_N9") (pintype "input"))
    )
    (net (code "32") (name "/DATA_CLK_N") (class "Default")
      (node (ref "U1") (pin "G1") (pinfunction "DATACLKN_G1") (pintype "input"))
    )
    (net (code "33") (name "/DATA_CLK_P") (class "Default")
      (node (ref "U1") (pin "G2") (pinfunction "DATACLKP_G2") (pintype "input"))
    )
    (net (code "34") (name "/IOUTA_N") (class "Default")
      (node (ref "C136") (pin "1") (pinfunction "1_1") (pintype "passive"))
      (node (ref "L12") (pin "1") (pinfunction "1_1") (pintype "passive"))
      (node (ref "R12") (pin "1") (pinfunction "1_1") (pintype "passive"))
      (node (ref "R258") (pin "1") (pinfunction "1_1") (pintype "passive"))
      (node (ref "U1") (pin "C14") (pinfunction "IOUTAN_C14") (pintype "output"))
    )
    (net (code "35") (name "/IOUTA_P") (class "Default")
      (node (ref "C136") (pin "2") (pinfunction "2_2") (pintype "passive"))
      (node (ref "L6") (pin "1") (pinfunction "1_1") (pintype "passive"))
      (node (ref "R11") (pin "1") (pinfunction "1_1") (pintype "passive"))
      (node (ref "R184") (pin "1") (pinfunction "1_1") (pintype "passive"))
      (node (ref "U1") (pin "B14") (pinfunction "IOUTAP_B14") (pintype "output"))
    )
    (net (code "36") (name "/IOUTB_N") (class "Default")
      (node (ref "C49") (pin "1") (pinfunction "1_1") (pintype "passive"))
      (node (ref "L23") (pin "1") (pinfunction "1_1") (pintype "passive"))
      (node (ref "R15") (pin "1") (pinfunction "1_1") (pintype "passive"))
      (node (ref "R264") (pin "1") (pinfunction "1_1") (pintype "passive"))
      (node (ref "U1") (pin "E14") (pinfunction "IOUTBN_E14") (pintype "output"))
    )
    (net (code "37") (name "/IOUTB_P") (class "Default")
      (node (ref "C49") (pin "2") (pinfunction "2_2") (pintype "passive"))
      (node (ref "L1") (pin "1") (pinfunction "1_1") (pintype "passive"))
      (node (ref "R13") (pin "1") (pinfunction "1_1") (pintype "passive"))
      (node (ref "R263") (pin "1") (pinfunction "1_1") (pintype "passive"))
      (node (ref "U1") (pin "F14") (pinfunction "IOUTBP_F14") (pintype "output"))
    )
    (net (code "38") (name "/IOUTC_N") (class "Default")
      (node (ref "C141") (pin "1") (pinfunction "1_1") (pintype "passive"))
      (node (ref "L39") (pin "1") (pinfunction "1_1") (pintype "passive"))
      (node (ref "R21") (pin "1") (pinfunction "1_1") (pintype "passive"))
      (node (ref "R266") (pin "1") (pinfunction "1_1") (pintype "passive"))
      (node (ref "U1") (pin "K14") (pinfunction "IOUTCN_K14") (pintype "output"))
    )
    (net (code "39") (name "/IOUTC_P") (class "Default")
      (node (ref "C141") (pin "2") (pinfunction "2_2") (pintype "passive"))
      (node (ref "L36") (pin "1") (pinfunction "1_1") (pintype "passive"))
      (node (ref "R16") (pin "1") (pinfunction "1_1") (pintype "passive"))
      (node (ref "R265") (pin "1") (pinfunction "1_1") (pintype "passive"))
      (node (ref "U1") (pin "J14") (pinfunction "IOUTCP_J14") (pintype "output"))
    )
    (net (code "40") (name "/IOUTD_N") (class "Default")
      (node (ref "C379") (pin "1") (pinfunction "1_1") (pintype "passive"))
      (node (ref "L55") (pin "1") (pinfunction "1_1") (pintype "passive"))
      (node (ref "R268") (pin "1") (pinfunction "1_1") (pintype "passive"))
      (node (ref "R31") (pin "1") (pinfunction "1_1") (pintype "passive"))
      (node (ref "U1") (pin "M14") (pinfunction "IOUTDN_M14") (pintype "output"))
    )
    (net (code "41") (name "/IOUTD_P") (class "Default")
      (node (ref "C379") (pin "2") (pinfunction "2_2") (pintype "passive"))
      (node (ref "L53") (pin "1") (pinfunction "1_1") (pintype "passive"))
      (node (ref "R24") (pin "1") (pinfunction "1_1") (pintype "passive"))
      (node (ref "R267") (pin "1") (pinfunction "1_1") (pintype "passive"))
      (node (ref "U1") (pin "N14") (pinfunction "IOUTDP_N14") (pintype "output"))
    )
    (net (code "42") (name "/ISTR_PARITYAB_N") (class "Default")
      (node (ref "U1") (pin "H1") (pinfunction "ISTRN/PARITYABN_H1") (pintype "input"))
    )
    (net (code "43") (name "/ISTR_PARITYAB_P") (class "Default")
      (node (ref "U1") (pin "H2") (pinfunction "ISTRP/PARITYABP_H2") (pintype "input"))
    )
    (net (code "44") (name "/LVDSA0_N") (class "Default")
      (node (ref "U1") (pin "G3") (pinfunction "DAB0N_(LSB)_G3") (pintype "input"))
    )
    (net (code "45") (name "/LVDSA0_P") (class "Default")
      (node (ref "U1") (pin "G4") (pinfunction "DAB0P_(LSB)_G4") (pintype "input"))
    )
    (net (code "46") (name "/LVDSA1_N") (class "Default")
      (node (ref "U1") (pin "F1") (pinfunction "DAB1N_F1") (pintype "input"))
    )
    (net (code "47") (name "/LVDSA1_P") (class "Default")
      (node (ref "U1") (pin "F2") (pinfunction "DAB1P_F2") (pintype "input"))
    )
    (net (code "48") (name "/LVDSA2_N") (class "Default")
      (node (ref "U1") (pin "F3") (pinfunction "DAB2N_F3") (pintype "input"))
    )
    (net (code "49") (name "/LVDSA2_P") (class "Default")
      (node (ref "U1") (pin "F4") (pinfunction "DAB2P_F4") (pintype "input"))
    )
    (net (code "50") (name "/LVDSA3_N") (class "Default")
      (node (ref "U1") (pin "E1") (pinfunction "DAB3N_E1") (pintype "input"))
    )
    (net (code "51") (name "/LVDSA3_P") (class "Default")
      (node (ref "U1") (pin "E2") (pinfunction "DAB3P_E2") (pintype "input"))
    )
    (net (code "52") (name "/LVDSA4_N") (class "Default")
      (node (ref "U1") (pin "E3") (pinfunction "DAB4N_E3") (pintype "input"))
    )
    (net (code "53") (name "/LVDSA4_P") (class "Default")
      (node (ref "U1") (pin "E4") (pinfunction "DAB4P_E4") (pintype "input"))
    )
    (net (code "54") (name "/LVDSA5_N") (class "Default")
      (node (ref "U1") (pin "D1") (pinfunction "DAB5N_D1") (pintype "input"))
    )
    (net (code "55") (name "/LVDSA5_P") (class "Default")
      (node (ref "U1") (pin "D2") (pinfunction "DAB5P_D2") (pintype "input"))
    )
    (net (code "56") (name "/LVDSA6_N") (class "Default")
      (node (ref "U1") (pin "D3") (pinfunction "DAB6N_D3") (pintype "input"))
    )
    (net (code "57") (name "/LVDSA6_P") (class "Default")
      (node (ref "U1") (pin "D4") (pinfunction "DAB6P_D4") (pintype "input"))
    )
    (net (code "58") (name "/LVDSA7_N") (class "Default")
      (node (ref "U1") (pin "C1") (pinfunction "DAB7N_C1") (pintype "input"))
    )
    (net (code "59") (name "/LVDSA7_P") (class "Default")
      (node (ref "U1") (pin "C2") (pinfunction "DAB7P_C2") (pintype "input"))
    )
    (net (code "60") (name "/LVDSA8_N") (class "Default")
      (node (ref "U1") (pin "C3") (pinfunction "DAB8N_C3") (pintype "input"))
    )
    (net (code "61") (name "/LVDSA8_P") (class "Default")
      (node (ref "U1") (pin "C4") (pinfunction "DAB8P_C4") (pintype "input"))
    )
    (net (code "62") (name "/LVDSA9_N") (class "Default")
      (node (ref "U1") (pin "B1") (pinfunction "DAB9N_B1") (pintype "input"))
    )
    (net (code "63") (name "/LVDSA9_P") (class "Default")
      (node (ref "U1") (pin "A1") (pinfunction "DAB9P_A1") (pintype "input"))
    )
    (net (code "64") (name "/LVDSA10_N") (class "Default")
      (node (ref "U1") (pin "B2") (pinfunction "DAB10N_B2") (pintype "input"))
    )
    (net (code "65") (name "/LVDSA10_P") (class "Default")
      (node (ref "U1") (pin "A2") (pinfunction "DAB10P_A2") (pintype "input"))
    )
    (net (code "66") (name "/LVDSA11_N") (class "Default")
      (node (ref "U1") (pin "B3") (pinfunction "DAB11N_B3") (pintype "input"))
    )
    (net (code "67") (name "/LVDSA11_P") (class "Default")
      (node (ref "U1") (pin "A3") (pinfunction "DAB11P_A3") (pintype "input"))
    )
    (net (code "68") (name "/LVDSA12_N") (class "Default")
      (node (ref "U1") (pin "B4") (pinfunction "DAB12N_B4") (pintype "input"))
    )
    (net (code "69") (name "/LVDSA12_P") (class "Default")
      (node (ref "U1") (pin "A4") (pinfunction "DAB12P_A4") (pintype "input"))
    )
    (net (code "70") (name "/LVDSA13_N") (class "Default")
      (node (ref "U1") (pin "B5") (pinfunction "DAB13N_B5") (pintype "input"))
    )
    (net (code "71") (name "/LVDSA13_P") (class "Default")
      (node (ref "U1") (pin "A5") (pinfunction "DAB13P_A5") (pintype "input"))
    )
    (net (code "72") (name "/LVDSA14_N") (class "Default")
      (node (ref "U1") (pin "B6") (pinfunction "DAB14N_B6") (pintype "input"))
    )
    (net (code "73") (name "/LVDSA14_P") (class "Default")
      (node (ref "U1") (pin "A6") (pinfunction "DAB14P_A6") (pintype "input"))
    )
    (net (code "74") (name "/LVDSA15_N") (class "Default")
      (node (ref "U1") (pin "B7") (pinfunction "DAB15N_(MSB)_B7") (pintype "input"))
    )
    (net (code "75") (name "/LVDSA15_P") (class "Default")
      (node (ref "U1") (pin "A7") (pinfunction "DAB15P_(MSB)_A7") (pintype "input"))
    )
    (net (code "76") (name "/LVDSB0_N") (class "Default")
      (node (ref "U1") (pin "P7") (pinfunction "DCD0N_(LSB)_P7") (pintype "input"))
    )
    (net (code "77") (name "/LVDSB0_P") (class "Default")
      (node (ref "U1") (pin "N7") (pinfunction "DCD0P_(LSB)_N7") (pintype "input"))
    )
    (net (code "78") (name "/LVDSB1_N") (class "Default")
      (node (ref "U1") (pin "P6") (pinfunction "DCD1N_P6") (pintype "input"))
    )
    (net (code "79") (name "/LVDSB1_P") (class "Default")
      (node (ref "U1") (pin "N6") (pinfunction "DCD1P_N6") (pintype "input"))
    )
    (net (code "80") (name "/LVDSB2_N") (class "Default")
      (node (ref "U1") (pin "P5") (pinfunction "DCD2N_P5") (pintype "input"))
    )
    (net (code "81") (name "/LVDSB2_P") (class "Default")
      (node (ref "U1") (pin "N5") (pinfunction "DCD2P_N5") (pintype "input"))
    )
    (net (code "82") (name "/LVDSB3_N") (class "Default")
      (node (ref "U1") (pin "P4") (pinfunction "DCD3N_P4") (pintype "input"))
    )
    (net (code "83") (name "/LVDSB3_P") (class "Default")
      (node (ref "U1") (pin "N4") (pinfunction "DCD3P_N4") (pintype "input"))
    )
    (net (code "84") (name "/LVDSB4_N") (class "Default")
      (node (ref "U1") (pin "P3") (pinfunction "DCD4N_P3") (pintype "input"))
    )
    (net (code "85") (name "/LVDSB4_P") (class "Default")
      (node (ref "U1") (pin "N3") (pinfunction "DCD4P_N3") (pintype "input"))
    )
    (net (code "86") (name "/LVDSB5_N") (class "Default")
      (node (ref "U1") (pin "P2") (pinfunction "DCD5N_P2") (pintype "input"))
    )
    (net (code "87") (name "/LVDSB5_P") (class "Default")
      (node (ref "U1") (pin "N2") (pinfunction "DCD5P_N2") (pintype "input"))
    )
    (net (code "88") (name "/LVDSB6_N") (class "Default")
      (node (ref "U1") (pin "P1") (pinfunction "DCD6N_P1") (pintype "input"))
    )
    (net (code "89") (name "/LVDSB6_P") (class "Default")
      (node (ref "U1") (pin "N1") (pinfunction "DCD6P_N1") (pintype "input"))
    )
    (net (code "90") (name "/LVDSB7_N") (class "Default")
      (node (ref "U1") (pin "M1") (pinfunction "DCD7N_M1") (pintype "input"))
    )
    (net (code "91") (name "/LVDSB7_P") (class "Default")
      (node (ref "U1") (pin "M2") (pinfunction "DCD7P_M2") (pintype "input"))
    )
    (net (code "92") (name "/LVDSB8_N") (class "Default")
      (node (ref "U1") (pin "M3") (pinfunction "DCD8N_M3") (pintype "input"))
    )
    (net (code "93") (name "/LVDSB8_P") (class "Default")
      (node (ref "U1") (pin "M4") (pinfunction "DCD8P_M4") (pintype "input"))
    )
    (net (code "94") (name "/LVDSB9_N") (class "Default")
      (node (ref "U1") (pin "L1") (pinfunction "DCD9N_L1") (pintype "input"))
    )
    (net (code "95") (name "/LVDSB9_P") (class "Default")
      (node (ref "U1") (pin "L2") (pinfunction "DCD9P_L2") (pintype "input"))
    )
    (net (code "96") (name "/LVDSB10_N") (class "Default")
      (node (ref "U1") (pin "L3") (pinfunction "DCD10N_L3") (pintype "input"))
    )
    (net (code "97") (name "/LVDSB10_P") (class "Default")
      (node (ref "U1") (pin "L4") (pinfunction "DCD10P_L4") (pintype "input"))
    )
    (net (code "98") (name "/LVDSB11_N") (class "Default")
      (node (ref "U1") (pin "K1") (pinfunction "DCD11N_K1") (pintype "input"))
    )
    (net (code "99") (name "/LVDSB11_P") (class "Default")
      (node (ref "U1") (pin "K2") (pinfunction "DCD11P_K2") (pintype "input"))
    )
    (net (code "100") (name "/LVDSB12_N") (class "Default")
      (node (ref "U1") (pin "K3") (pinfunction "DCD12N_K3") (pintype "input"))
    )
    (net (code "101") (name "/LVDSB12_P") (class "Default")
      (node (ref "U1") (pin "K4") (pinfunction "DCD12P_K4") (pintype "input"))
    )
    (net (code "102") (name "/LVDSB13_N") (class "Default")
      (node (ref "U1") (pin "J1") (pinfunction "DCD13N_J1") (pintype "input"))
    )
    (net (code "103") (name "/LVDSB13_P") (class "Default")
      (node (ref "U1") (pin "J2") (pinfunction "DCD13P_J2") (pintype "input"))
    )
    (net (code "104") (name "/LVDSB14_N") (class "Default")
      (node (ref "U1") (pin "J3") (pinfunction "DCD14N_J3") (pintype "input"))
    )
    (net (code "105") (name "/LVDSB14_P") (class "Default")
      (node (ref "U1") (pin "J4") (pinfunction "DCD14P_J4") (pintype "input"))
    )
    (net (code "106") (name "/LVDSB15_N") (class "Default")
      (node (ref "U1") (pin "H3") (pinfunction "DCD15N_(MSB)_H3") (pintype "input"))
    )
    (net (code "107") (name "/LVDSB15_P") (class "Default")
      (node (ref "U1") (pin "H4") (pinfunction "DCD15P_(MSB)_H4") (pintype "input"))
    )
    (net (code "108") (name "/OSTR_N") (class "Default")
      (node (ref "C360") (pin "1") (pinfunction "1_1") (pintype "passive"))
    )
    (net (code "109") (name "/OSTR_P") (class "Default")
      (node (ref "C363") (pin "1") (pinfunction "1_1") (pintype "passive"))
    )
    (net (code "110") (name "/PARITYCD_N") (class "Default")
      (node (ref "U1") (pin "P8") (pinfunction "PARITYCDN_P8") (pintype "input"))
    )
    (net (code "111") (name "/PARITYCD_P") (class "Default")
      (node (ref "U1") (pin "N8") (pinfunction "PARITYCDP_N8") (pintype "input"))
    )
    (net (code "112") (name "/SYNC_N") (class "Default")
      (node (ref "U1") (pin "B8") (pinfunction "SYNCN_B8") (pintype "input"))
    )
    (net (code "113") (name "/SYNC_P") (class "Default")
      (node (ref "U1") (pin "A8") (pinfunction "SYNCP_A8") (pintype "input"))
    )
    (net (code "117") (name "GND") (class "Default")
      (node (ref "C145") (pin "1") (pinfunction "1_1") (pintype "passive"))
      (node (ref "C146") (pin "1") (pinfunction "1_1") (pintype "passive"))
      (node (ref "C25") (pin "2") (pinfunction "2_2") (pintype "passive"))
      (node (ref "C32") (pin "2") (pinfunction "2_2") (pintype "passive"))
      (node (ref "J13") (pin "2") (pinfunction "2_2") (pintype "bidirectional"))
      (node (ref "J15") (pin "2") (pinfunction "2_2") (pintype "bidirectional"))
      (node (ref "R11") (pin "2") (pinfunction "2_2") (pintype "passive"))
      (node (ref "R12") (pin "2") (pinfunction "2_2") (pintype "passive"))
      (node (ref "R13") (pin "2") (pinfunction "2_2") (pintype "passive"))
      (node (ref "R15") (pin "2") (pinfunction "2_2") (pintype "passive"))
      (node (ref "R16") (pin "2") (pinfunction "2_2") (pintype "passive"))
      (node (ref "R184") (pin "2") (pinfunction "2_2") (pintype "passive"))
      (node (ref "R21") (pin "2") (pinfunction "2_2") (pintype "passive"))
      (node (ref "R24") (pin "2") (pinfunction "2_2") (pintype "passive"))
      (node (ref "R250") (pin "1") (pinfunction "1_1") (pintype "passive"))
      (node (ref "R251") (pin "1") (pinfunction "1_1") (pintype "passive"))
      (node (ref "R253") (pin "1") (pinfunction "1_1") (pintype "passive"))
      (node (ref "R254") (pin "1") (pinfunction "1_1") (pintype "passive"))
      (node (ref "R258") (pin "2") (pinfunction "2_2") (pintype "passive"))
      (node (ref "R263") (pin "2") (pinfunction "2_2") (pintype "passive"))
      (node (ref "R264") (pin "2") (pinfunction "2_2") (pintype "passive"))
      (node (ref "R265") (pin "2") (pinfunction "2_2") (pintype "passive"))
      (node (ref "R266") (pin "2") (pinfunction "2_2") (pintype "passive"))
      (node (ref "R267") (pin "2") (pinfunction "2_2") (pintype "passive"))
      (node (ref "R268") (pin "2") (pinfunction "2_2") (pintype "passive"))
      (node (ref "R31") (pin "2") (pinfunction "2_2") (pintype "passive"))
      (node (ref "R35") (pin "2") (pinfunction "2_2") (pintype "passive"))
      (node (ref "R36") (pin "2") (pinfunction "2_2") (pintype "passive"))
      (node (ref "TR10") (pin "2") (pinfunction "NC_2") (pintype "passive"))
      (node (ref "TR11") (pin "2") (pinfunction "NC_2") (pintype "passive"))
      (node (ref "TR3") (pin "2") (pinfunction "SCT_2") (pintype "passive"))
      (node (ref "TR4") (pin "2") (pinfunction "SCT_2") (pintype "passive"))
      (node (ref "TR5") (pin "2") (pinfunction "SCT_2") (pintype "passive"))
      (node (ref "TR7") (pin "2") (pinfunction "NC_2") (pintype "passive"))
      (node (ref "TR8") (pin "2") (pinfunction "SCT_2") (pintype "passive"))
      (node (ref "TR9") (pin "2") (pinfunction "NC_2") (pintype "passive"))
    )
    (net (code "118") (name "Net-(C32-Pad1)") (class "Default")
      (node (ref "C32") (pin "1") (pinfunction "1_1") (pintype "passive"))
      (node (ref "R232") (pin "2") (pinfunction "2_2") (pintype "passive"))
    )
    (net (code "119") (name "Net-(C36-Pad1)") (class "Default")
      (node (ref "C36") (pin "1") (pinfunction "1_1") (pintype "passive"))
      (node (ref "L30") (pin "2") (pinfunction "2_2") (pintype "passive"))
      (node (ref "R269") (pin "2") (pinfunction "2_2") (pintype "passive"))
      (node (ref "R39") (pin "1") (pinfunction "1_1") (pintype "passive"))
    )
    (net (code "120") (name "Net-(C36-Pad2)") (class "Default")
      (node (ref "C36") (pin "2") (pinfunction "2_2") (pintype "passive"))
      (node (ref "L28") (pin "2") (pinfunction "2_2") (pintype "passive"))
      (node (ref "R248") (pin "2") (pinfunction "2_2") (pintype "passive"))
      (node (ref "R37") (pin "1") (pinfunction "1_1") (pintype "passive"))
    )
    (net (code "121") (name "Net-(C137-Pad1)") (class "Default")
      (node (ref "C137") (pin "1") (pinfunction "1_1") (pintype "passive"))
      (node (ref "L23") (pin "2") (pinfunction "2_2") (pintype "passive"))
      (node (ref "L32") (pin "1") (pinfunction "1_1") (pintype "passive"))
    )
    (net (code "122") (name "Net-(C137-Pad2)") (class "Default")
      (node (ref "C137") (pin "2") (pinfunction "2_2") (pintype "passive"))
      (node (ref "L1") (pin "2") (pinfunction "2_2") (pintype "passive"))
      (node (ref "L21") (pin "1") (pinfunction "1_1") (pintype "passive"))
    )
    (net (code "123") (name "Net-(C140-Pad1)") (class "Default")
      (node (ref "C140") (pin "1") (pinfunction "1_1") (pintype "passive"))
      (node (ref "L32") (pin "2") (pinfunction "2_2") (pintype "passive"))
      (node (ref "R271") (pin "2") (pinfunction "2_2") (pintype "passive"))
      (node (ref "R54") (pin "1") (pinfunction "1_1") (pintype "passive"))
    )
    (net (code "124") (name "Net-(C140-Pad2)") (class "Default")
      (node (ref "C140") (pin "2") (pinfunction "2_2") (pintype "passive"))
      (node (ref "L21") (pin "2") (pinfunction "2_2") (pintype "passive"))
      (node (ref "R270") (pin "2") (pinfunction "2_2") (pintype "passive"))
      (node (ref "R40") (pin "1") (pinfunction "1_1") (pintype "passive"))
    )
    (net (code "125") (name "Net-(C146-Pad2)") (class "Default")
      (node (ref "C146") (pin "2") (pinfunction "2_2") (pintype "passive"))
      (node (ref "R232") (pin "1") (pinfunction "1_1") (pintype "passive"))
      (node (ref "R63") (pin "1") (pinfunction "1_1") (pintype "passive"))
    )
    (net (code "126") (name "Net-(C151-Pad1)") (class "Default")
      (node (ref "C151") (pin "1") (pinfunction "1_1") (pintype "passive"))
      (node (ref "L39") (pin "2") (pinfunction "2_2") (pintype "passive"))
      (node (ref "L40") (pin "1") (pinfunction "1_1") (pintype "passive"))
    )
    (net (code "127") (name "Net-(C151-Pad2)") (class "Default")
      (node (ref "C151") (pin "2") (pinfunction "2_2") (pintype "passive"))
      (node (ref "L36") (pin "2") (pinfunction "2_2") (pintype "passive"))
      (node (ref "L37") (pin "1") (pinfunction "1_1") (pintype "passive"))
    )
    (net (code "128") (name "Net-(C152-Pad1)") (class "Default")
      (node (ref "C152") (pin "1") (pinfunction "1_1") (pintype "passive"))
      (node (ref "L40") (pin "2") (pinfunction "2_2") (pintype "passive"))
      (node (ref "R273") (pin "2") (pinfunction "2_2") (pintype "passive"))
      (node (ref "R67") (pin "1") (pinfunction "1_1") (pintype "passive"))
    )
    (net (code "129") (name "Net-(C152-Pad2)") (class "Default")
      (node (ref "C152") (pin "2") (pinfunction "2_2") (pintype "passive"))
      (node (ref "L37") (pin "2") (pinfunction "2_2") (pintype "passive"))
      (node (ref "R272") (pin "2") (pinfunction "2_2") (pintype "passive"))
      (node (ref "R61") (pin "1") (pinfunction "1_1") (pintype "passive"))
    )
    (net (code "130") (name "Net-(C378-Pad1)") (class "Default")
      (node (ref "C378") (pin "1") (pinfunction "1_1") (pintype "passive"))
      (node (ref "L12") (pin "2") (pinfunction "2_2") (pintype "passive"))
      (node (ref "L30") (pin "1") (pinfunction "1_1") (pintype "passive"))
    )
    (net (code "131") (name "Net-(C378-Pad2)") (class "Default")
      (node (ref "C378") (pin "2") (pinfunction "2_2") (pintype "passive"))
      (node (ref "L28") (pin "1") (pinfunction "1_1") (pintype "passive"))
      (node (ref "L6") (pin "2") (pinfunction "2_2") (pintype "passive"))
    )
    (net (code "132") (name "Net-(C380-Pad1)") (class "Default")
      (node (ref "C380") (pin "1") (pinfunction "1_1") (pintype "passive"))
      (node (ref "L55") (pin "2") (pinfunction "2_2") (pintype "passive"))
      (node (ref "L56") (pin "1") (pinfunction "1_1") (pintype "passive"))
    )
    (net (code "133") (name "Net-(C380-Pad2)") (class "Default")
      (node (ref "C380") (pin "2") (pinfunction "2_2") (pintype "passive"))
      (node (ref "L53") (pin "2") (pinfunction "2_2") (pintype "passive"))
      (node (ref "L54") (pin "1") (pinfunction "1_1") (pintype "passive"))
    )
    (net (code "134") (name "Net-(C381-Pad1)") (class "Default")
      (node (ref "C381") (pin "1") (pinfunction "1_1") (pintype "passive"))
      (node (ref "L56") (pin "2") (pinfunction "2_2") (pintype "passive"))
      (node (ref "R275") (pin "2") (pinfunction "2_2") (pintype "passive"))
      (node (ref "R86") (pin "1") (pinfunction "1_1") (pintype "passive"))
    )
    (net (code "135") (name "Net-(C381-Pad2)") (class "Default")
      (node (ref "C381") (pin "2") (pinfunction "2_2") (pintype "passive"))
      (node (ref "L54") (pin "2") (pinfunction "2_2") (pintype "passive"))
      (node (ref "R274") (pin "2") (pinfunction "2_2") (pintype "passive"))
      (node (ref "R76") (pin "1") (pinfunction "1_1") (pintype "passive"))
    )
    (net (code "136") (name "Net-(J13-Pad1)") (class "Default")
      (node (ref "J13") (pin "1") (pinfunction "1_1") (pintype "bidirectional"))
      (node (ref "R246") (pin "1") (pinfunction "1_1") (pintype "passive"))
    )
    (net (code "137") (name "Net-(J15-Pad1)") (class "Default")
      (node (ref "J15") (pin "1") (pinfunction "1_1") (pintype "bidirectional"))
      (node (ref "R247") (pin "1") (pinfunction "1_1") (pintype "passive"))
    )
    (net (code "138") (name "Net-(R34-Pad2)") (class "Default")
      (node (ref "R34") (pin "2") (pinfunction "2_2") (pintype "passive"))
      (node (ref "R35") (pin "1") (pinfunction "1_1") (pintype "passive"))
    )
    (net (code "139") (name "Net-(TR3-P)") (class "Default")
      (node (ref "C382") (pin "1") (pinfunction "1_1") (pintype "passive"))
      (node (ref "R249") (pin "2") (pinfunction "2_2") (pintype "passive"))
      (node (ref "R3") (pin "2") (pinfunction "2_2") (pintype "passive"))
      (node (ref "R59") (pin "1") (pinfunction "1_1") (pintype "passive"))
      (node (ref "TR3") (pin "4") (pinfunction "P_4") (pintype "passive"))
      (node (ref "TR7") (pin "4") (pinfunction "P_4") (pintype "passive"))
    )
    (net (code "140") (name "Net-(TR3-PDOT)") (class "Default")
      (node (ref "C383") (pin "1") (pinfunction "1_1") (pintype "passive"))
      (node (ref "R17") (pin "2") (pinfunction "2_2") (pintype "passive"))
      (node (ref "R2") (pin "1") (pinfunction "1_1") (pintype "passive"))
      (node (ref "R250") (pin "2") (pinfunction "2_2") (pintype "passive"))
      (node (ref "TR3") (pin "6") (pinfunction "PDOT_6") (pintype "passive"))
      (node (ref "TR7") (pin "6") (pinfunction "PDOT_6") (pintype "passive"))
    )
    (net (code "141") (name "Net-(TR8-P)") (class "Default")
      (node (ref "C385") (pin "1") (pinfunction "1_1") (pintype "passive"))
      (node (ref "R228") (pin "2") (pinfunction "2_2") (pintype "passive"))
      (node (ref "R251") (pin "2") (pinfunction "2_2") (pintype "passive"))
      (node (ref "R50") (pin "1") (pinfunction "1_1") (pintype "passive"))
      (node (ref "TR8") (pin "4") (pinfunction "P_4") (pintype "passive"))
      (node (ref "TR9") (pin "4") (pinfunction "P_4") (pintype "passive"))
    )
    (net (code "142") (name "Net-(TR8-PDOT)") (class "Default")
      (node (ref "C384") (pin "1") (pinfunction "1_1") (pintype "passive"))
      (node (ref "R227") (pin "2") (pinfunction "2_2") (pintype "passive"))
      (node (ref "R246") (pin "2") (pinfunction "2_2") (pintype "passive"))
      (node (ref "R32") (pin "1") (pinfunction "1_1") (pintype "passive"))
      (node (ref "TR8") (pin "6") (pinfunction "PDOT_6") (pintype "passive"))
      (node (ref "TR9") (pin "6") (pinfunction "PDOT_6") (pintype "passive"))
    )
    (net (code "143") (name "Net-(TR10-P)") (class "Default")
      (node (ref "C386") (pin "1") (pinfunction "1_1") (pintype "passive"))
      (node (ref "R252") (pin "2") (pinfunction "2_2") (pintype "passive"))
      (node (ref "R62") (pin "1") (pinfunction "1_1") (pintype "passive"))
      (node (ref "R68") (pin "2") (pinfunction "2_2") (pintype "passive"))
      (node (ref "TR10") (pin "4") (pinfunction "P_4") (pintype "passive"))
      (node (ref "TR4") (pin "4") (pinfunction "P_4") (pintype "passive"))
    )
    (net (code "144") (name "Net-(TR10-PDOT)") (class "Default")
      (node (ref "C387") (pin "1") (pinfunction "1_1") (pintype "passive"))
      (node (ref "R253") (pin "2") (pinfunction "2_2") (pintype "passive"))
      (node (ref "R66") (pin "1") (pinfunction "1_1") (pintype "passive"))
      (node (ref "R69") (pin "2") (pinfunction "2_2") (pintype "passive"))
      (node (ref "TR10") (pin "6") (pinfunction "PDOT_6") (pintype "passive"))
      (node (ref "TR4") (pin "6") (pinfunction "PDOT_6") (pintype "passive"))
    )
    (net (code "145") (name "Net-(TR11-P)") (class "Default")
      (node (ref "C389") (pin "1") (pinfunction "1_1") (pintype "passive"))
      (node (ref "R230") (pin "2") (pinfunction "2_2") (pintype "passive"))
      (node (ref "R254") (pin "2") (pinfunction "2_2") (pintype "passive"))
      (node (ref "R85") (pin "1") (pinfunction "1_1") (pintype "passive"))
      (node (ref "TR11") (pin "4") (pinfunction "P_4") (pintype "passive"))
      (node (ref "TR5") (pin "4") (pinfunction "P_4") (pintype "passive"))
    )
    (net (code "146") (name "Net-(TR11-PDOT)") (class "Default")
      (node (ref "C388") (pin "1") (pinfunction "1_1") (pintype "passive"))
      (node (ref "R229") (pin "2") (pinfunction "2_2") (pintype "passive"))
      (node (ref "R247") (pin "2") (pinfunction "2_2") (pintype "passive"))
      (node (ref "R77") (pin "1") (pinfunction "1_1") (pintype "passive"))
      (node (ref "TR11") (pin "6") (pinfunction "PDOT_6") (pintype "passive"))
      (node (ref "TR5") (pin "6") (pinfunction "PDOT_6") (pintype "passive"))
    )
    (net (code "147") (name "Net-(U1C-BIASJ)") (class "Default")
      (node (ref "R34") (pin "1") (pinfunction "1_1") (pintype "passive"))
      (node (ref "U1") (pin "H12") (pinfunction "BIASJ_H12") (pintype "passive"))
    )
    (net (code "148") (name "Net-(U1C-EXTIO)") (class "Default")
      (node (ref "C145") (pin "2") (pinfunction "2_2") (pintype "passive"))
      (node (ref "C25") (pin "1") (pinfunction "1_1") (pintype "passive"))
      (node (ref "U1") (pin "G12") (pinfunction "EXTIO_G12") (pintype "bidirectional"))
    )
    (net (code "149") (name "Net-(U1C-LPF)") (class "Default")
      (node (ref "R63") (pin "2") (pinfunction "2_2") (pintype "passive"))
      (node (ref "U1") (pin "D12") (pinfunction "LPF_D12") (pintype "passive"))
    )
    (net (code "150") (name "Net-(U1C-OSTRN)") (class "Default")
      (node (ref "C360") (pin "2") (pinfunction "2_2") (pintype "passive"))
      (node (ref "R65") (pin "1") (pinfunction "1_1") (pintype "passive"))
      (node (ref "U1") (pin "B9") (pinfunction "OSTRN_B9") (pintype "input"))
    )
    (net (code "151") (name "Net-(U1C-OSTRP)") (class "Default")
      (node (ref "C363") (pin "2") (pinfunction "2_2") (pintype "passive"))
      (node (ref "R65") (pin "2") (pinfunction "2_2") (pintype "passive"))
      (node (ref "U1") (pin "A9") (pinfunction "OSTRP_A9") (pintype "input"))
    )
    (net (code "152") (name "P3V3") (class "Default")
      (node (ref "R231") (pin "2") (pinfunction "2_2") (pintype "passive"))
    )
    (net (code "153") (name "unconnected-(U1C-TESTMODE-PadL11)") (class "Default")
      (node (ref "U1") (pin "L11") (pinfunction "TESTMODE_L11") (pintype "passive+no_connect"))
    )
  )
)
